# AI_XiaoZhi_4G.net
KiCad netlist of a schematic drawn in Altium Designer
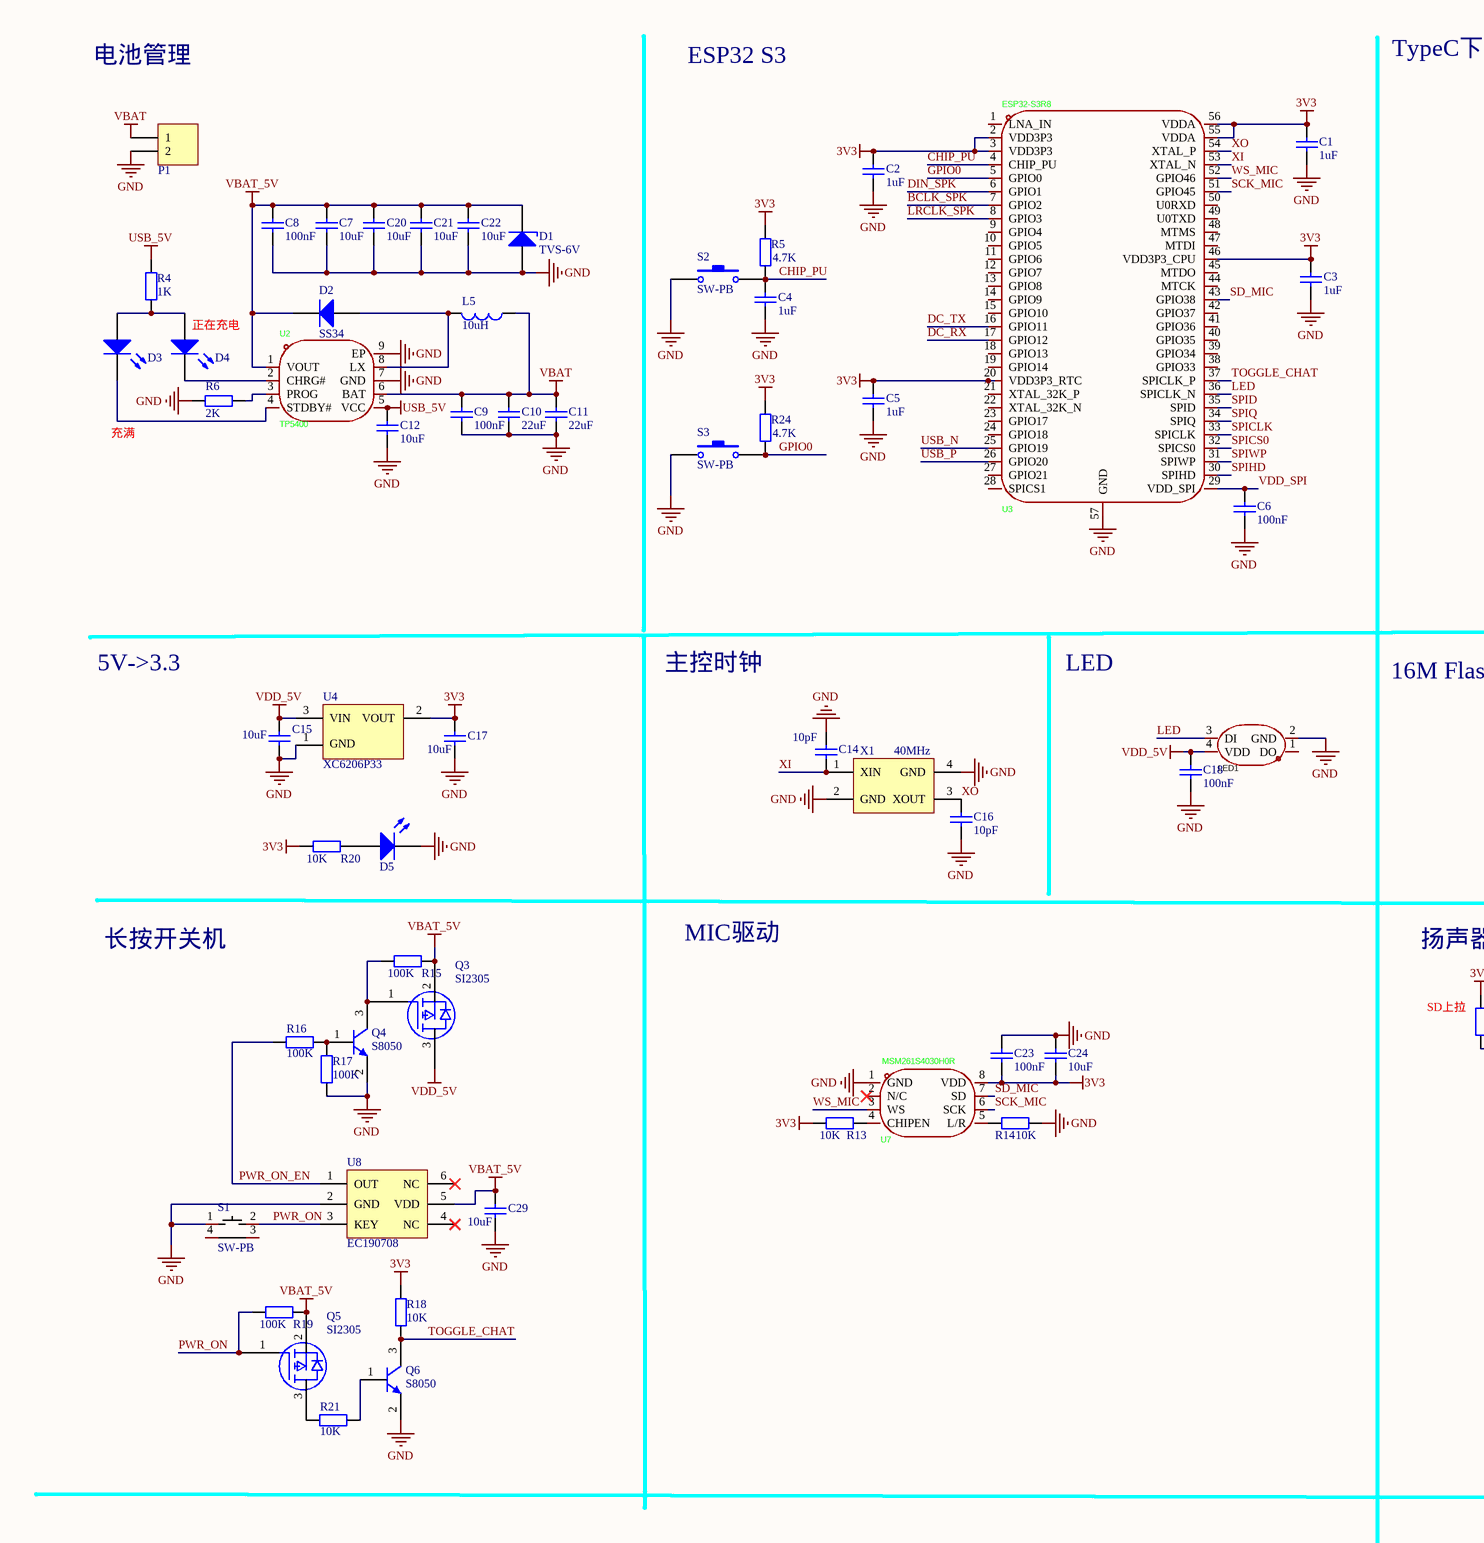
[diagram p0: AI_XiaoZhi_4G.SchDoc, left]
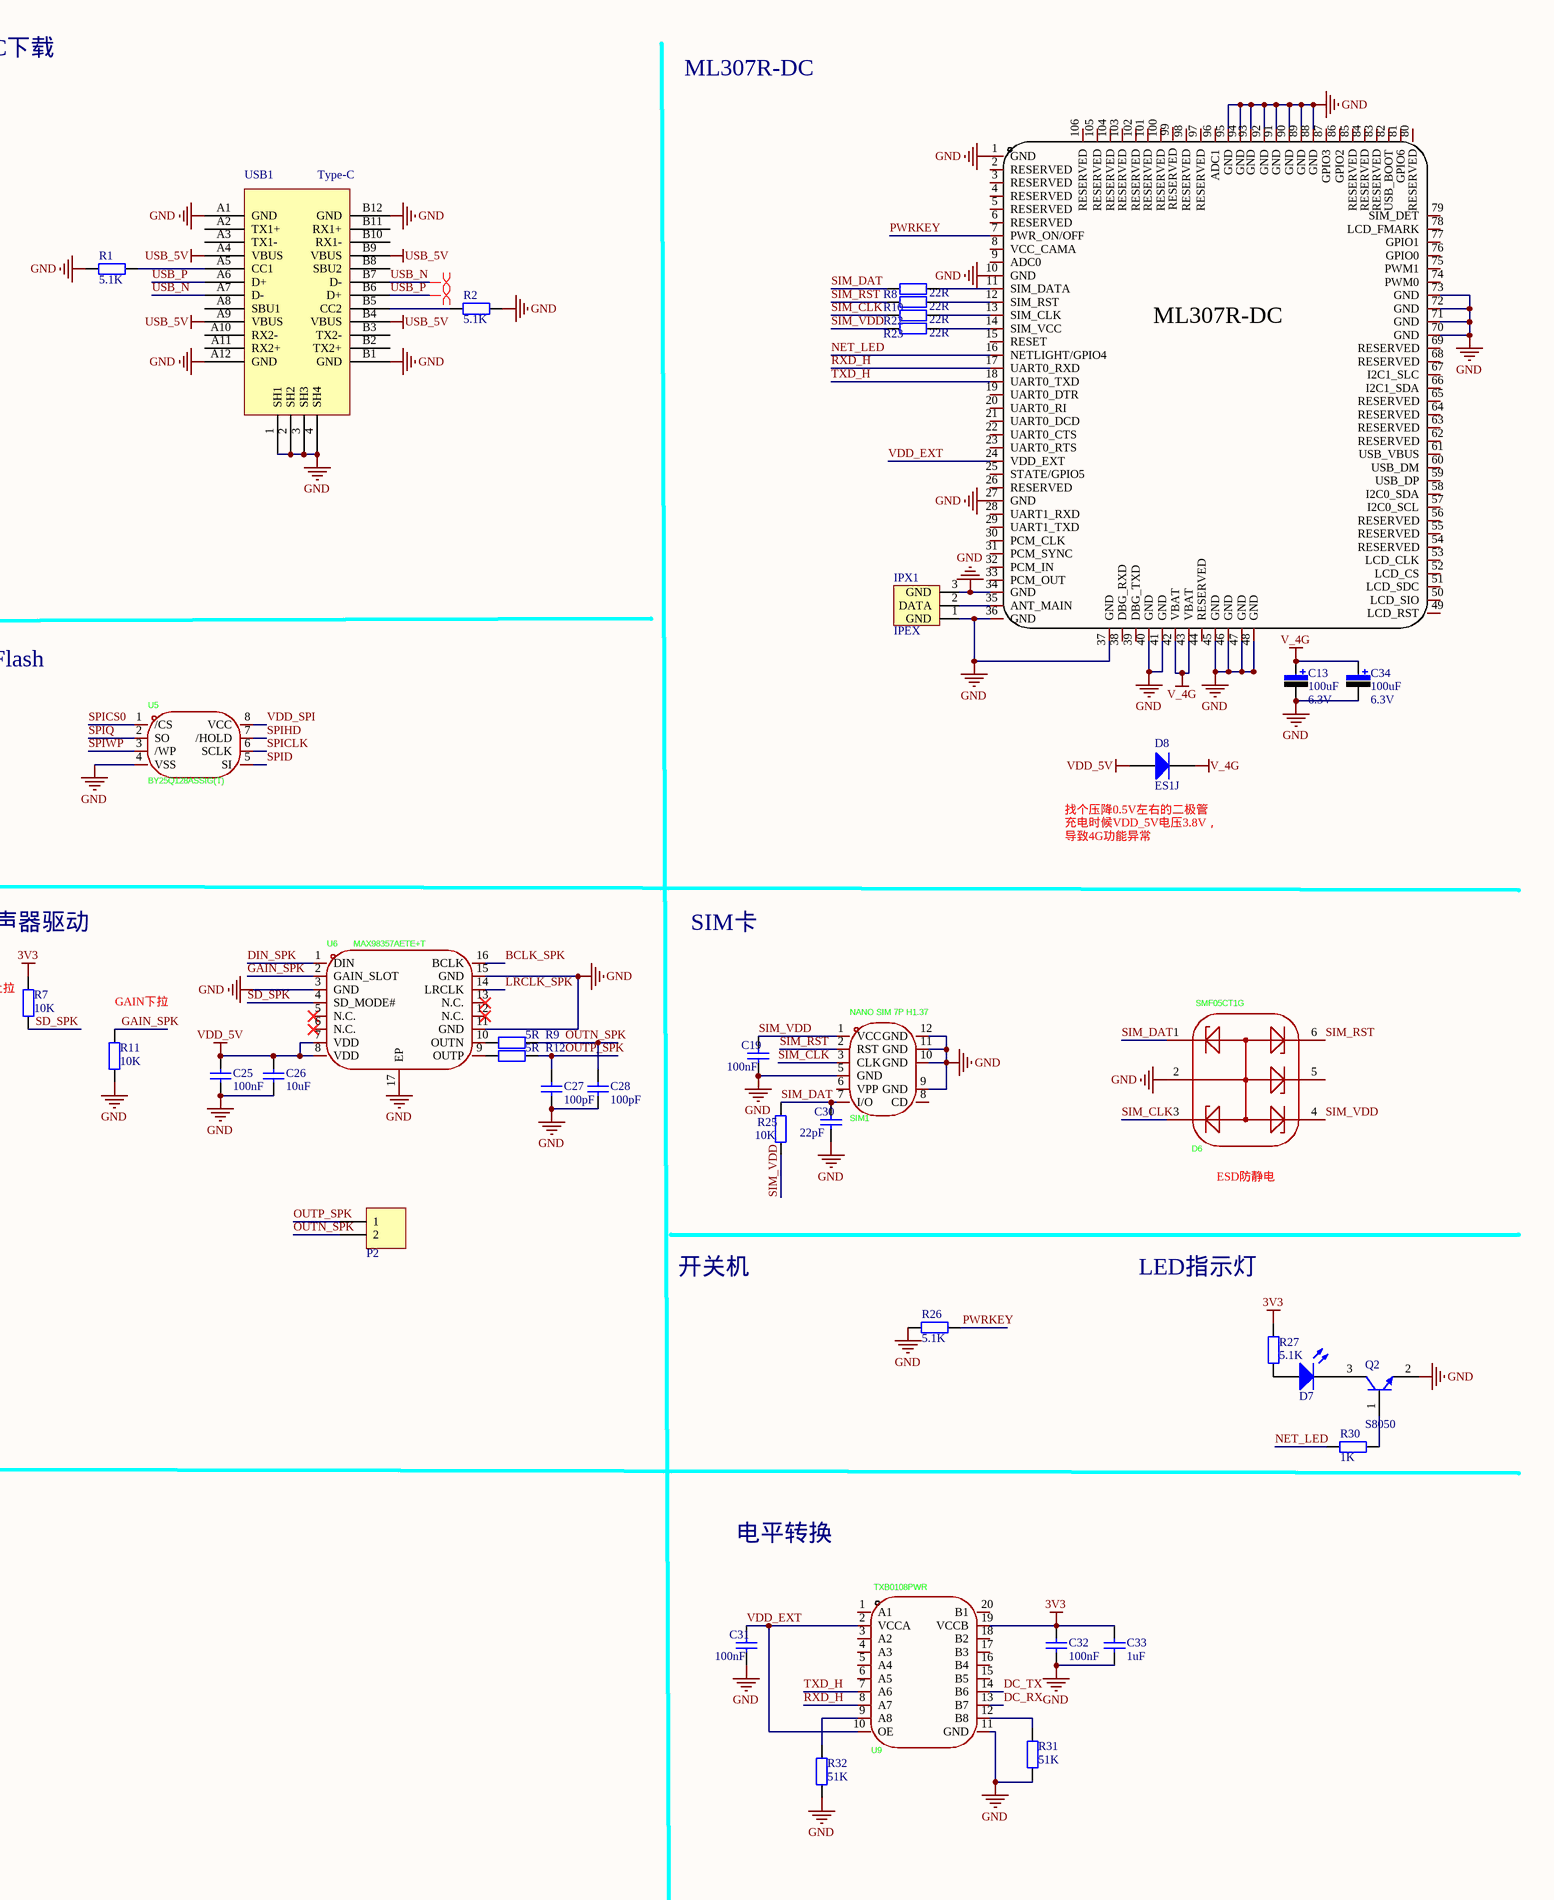
[diagram p1: AI_XiaoZhi_4G.SchDoc, right]

(export (version "E")
  (design (tool "Eeschema 10.0.6"))
  (components
    (comp (ref "C1")
      (value "1uF")
      (footprint "PCBPcblib_MXJ:0603-C")
      (description "无极性电容")
      (fields (field (name "Comment") "CAP") (field (name "PUBLISHER") "Altium Limited"))
      (libsource (lib "PCBSchlib_MXJ") (part "CAP"))
    )
    (comp (ref "C2")
      (value "1uF")
      (footprint "PCBPcblib_MXJ:0603-C")
      (description "无极性电容")
      (fields (field (name "Comment") "CAP") (field (name "PUBLISHER") "Altium Limited"))
      (libsource (lib "PCBSchlib_MXJ") (part "CAP"))
    )
    (comp (ref "C3")
      (value "1uF")
      (footprint "PCBPcblib_MXJ:0603-C")
      (description "无极性电容")
      (fields (field (name "Comment") "CAP") (field (name "PUBLISHER") "Altium Limited"))
      (libsource (lib "PCBSchlib_MXJ") (part "CAP"))
    )
    (comp (ref "C4")
      (value "1uF")
      (footprint "PCBPcblib_MXJ:0603-C")
      (description "无极性电容")
      (fields (field (name "Comment") "CAP") (field (name "PUBLISHER") "Altium Limited"))
      (libsource (lib "PCBSchlib_MXJ") (part "CAP"))
    )
    (comp (ref "C5")
      (value "1uF")
      (footprint "PCBPcblib_MXJ:0603-C")
      (description "无极性电容")
      (fields (field (name "Comment") "CAP") (field (name "PUBLISHER") "Altium Limited"))
      (libsource (lib "PCBSchlib_MXJ") (part "CAP"))
    )
    (comp (ref "C6")
      (value "100nF")
      (footprint "PCBPcblib_MXJ:0603-C")
      (description "无极性电容")
      (fields (field (name "Comment") "CAP") (field (name "PUBLISHER") "Altium Limited"))
      (libsource (lib "PCBSchlib_MXJ") (part "CAP"))
    )
    (comp (ref "C7")
      (value "10uF")
      (footprint "PCBPcblib_MXJ:0603-C")
      (description "无极性电容")
      (fields (field (name "Comment") "CAP") (field (name "PUBLISHER") "Altium Limited"))
      (libsource (lib "PCBSchlib_MXJ") (part "CAP"))
    )
    (comp (ref "C8")
      (value "100nF")
      (footprint "PCBPcblib_MXJ:0603-C")
      (description "无极性电容")
      (fields (field (name "Comment") "CAP") (field (name "PUBLISHER") "Altium Limited"))
      (libsource (lib "PCBSchlib_MXJ") (part "CAP"))
    )
    (comp (ref "C9")
      (value "100nF")
      (footprint "PCBPcblib_MXJ:0603-C")
      (description "无极性电容")
      (fields (field (name "Comment") "CAP") (field (name "PUBLISHER") "Altium Limited"))
      (libsource (lib "PCBSchlib_MXJ") (part "CAP"))
    )
    (comp (ref "C10")
      (value "22uF")
      (footprint "PCBPcblib_MXJ:0603-C")
      (description "无极性电容")
      (fields (field (name "Comment") "CAP") (field (name "PUBLISHER") "Altium Limited"))
      (libsource (lib "PCBSchlib_MXJ") (part "CAP"))
    )
    (comp (ref "C11")
      (value "22uF")
      (footprint "PCBPcblib_MXJ:0603-C")
      (description "无极性电容")
      (fields (field (name "Comment") "CAP") (field (name "PUBLISHER") "Altium Limited"))
      (libsource (lib "PCBSchlib_MXJ") (part "CAP"))
    )
    (comp (ref "C12")
      (value "10uF")
      (footprint "PCBPcblib_MXJ:0603-C")
      (description "无极性电容")
      (fields (field (name "Comment") "CAP") (field (name "PUBLISHER") "Altium Limited"))
      (libsource (lib "PCBSchlib_MXJ") (part "CAP"))
    )
    (comp (ref "C13")
      (value "100uF")
      (footprint "PCBPcblib_MXJ:CASE-A_3216")
      (description "极性电解电容")
      (fields
        (field (name "VOL") "6.3V")
        (field (name "Comment") "CAP-P")
        (field (name "PUBLISHER") "Altium Limited")
      )
      (libsource (lib "PCBSchlib_MXJ") (part "CAP-P"))
    )
    (comp (ref "C14")
      (value "10pF")
      (footprint "PCBPcblib_MXJ:0603-C")
      (description "无极性电容")
      (fields (field (name "Comment") "CAP") (field (name "PUBLISHER") "Altium Limited"))
      (libsource (lib "PCBSchlib_MXJ") (part "CAP"))
    )
    (comp (ref "C15")
      (value "10uF")
      (footprint "PCBPcblib_MXJ:0603-C")
      (description "无极性电容")
      (fields (field (name "Comment") "CAP") (field (name "PUBLISHER") "Altium Limited"))
      (libsource (lib "PCBSchlib_MXJ") (part "CAP"))
    )
    (comp (ref "C16")
      (value "10pF")
      (footprint "PCBPcblib_MXJ:0603-C")
      (description "无极性电容")
      (fields (field (name "Comment") "CAP") (field (name "PUBLISHER") "Altium Limited"))
      (libsource (lib "PCBSchlib_MXJ") (part "CAP"))
    )
    (comp (ref "C17")
      (value "10uF")
      (footprint "PCBPcblib_MXJ:0603-C")
      (description "无极性电容")
      (fields (field (name "Comment") "CAP") (field (name "PUBLISHER") "Altium Limited"))
      (libsource (lib "PCBSchlib_MXJ") (part "CAP"))
    )
    (comp (ref "C18")
      (value "100nF")
      (footprint "PCBPcblib_MXJ:0603-C")
      (description "无极性电容")
      (fields (field (name "Comment") "CAP") (field (name "PUBLISHER") "Altium Limited"))
      (libsource (lib "PCBSchlib_MXJ") (part "CAP"))
    )
    (comp (ref "C19")
      (value "100nF")
      (footprint "PCBPcblib_MXJ:0603-C")
      (description "无极性电容")
      (fields (field (name "Comment") "CAP") (field (name "PUBLISHER") "Altium Limited"))
      (libsource (lib "PCBSchlib_MXJ") (part "CAP"))
    )
    (comp (ref "C20")
      (value "10uF")
      (footprint "PCBPcblib_MXJ:0603-C")
      (description "无极性电容")
      (fields (field (name "Comment") "CAP") (field (name "PUBLISHER") "Altium Limited"))
      (libsource (lib "PCBSchlib_MXJ") (part "CAP"))
    )
    (comp (ref "C21")
      (value "10uF")
      (footprint "PCBPcblib_MXJ:0603-C")
      (description "无极性电容")
      (fields (field (name "Comment") "CAP") (field (name "PUBLISHER") "Altium Limited"))
      (libsource (lib "PCBSchlib_MXJ") (part "CAP"))
    )
    (comp (ref "C22")
      (value "10uF")
      (footprint "PCBPcblib_MXJ:0603-C")
      (description "无极性电容")
      (fields (field (name "Comment") "CAP") (field (name "PUBLISHER") "Altium Limited"))
      (libsource (lib "PCBSchlib_MXJ") (part "CAP"))
    )
    (comp (ref "C23")
      (value "100nF")
      (footprint "PCBPcblib_MXJ:0603-C")
      (description "无极性电容")
      (fields (field (name "Comment") "CAP") (field (name "PUBLISHER") "Altium Limited"))
      (libsource (lib "PCBSchlib_MXJ") (part "CAP"))
    )
    (comp (ref "C24")
      (value "10uF")
      (footprint "PCBPcblib_MXJ:0603-C")
      (description "无极性电容")
      (fields (field (name "Comment") "CAP") (field (name "PUBLISHER") "Altium Limited"))
      (libsource (lib "PCBSchlib_MXJ") (part "CAP"))
    )
    (comp (ref "C25")
      (value "100nF")
      (footprint "PCBPcblib_MXJ:0603-C")
      (description "无极性电容")
      (fields (field (name "Comment") "CAP") (field (name "PUBLISHER") "Altium Limited"))
      (libsource (lib "PCBSchlib_MXJ") (part "CAP"))
    )
    (comp (ref "C26")
      (value "10uF")
      (footprint "PCBPcblib_MXJ:0603-C")
      (description "无极性电容")
      (fields (field (name "Comment") "CAP") (field (name "PUBLISHER") "Altium Limited"))
      (libsource (lib "PCBSchlib_MXJ") (part "CAP"))
    )
    (comp (ref "C27")
      (value "100pF")
      (footprint "PCBPcblib_MXJ:0603-C")
      (description "无极性电容")
      (fields (field (name "Comment") "CAP") (field (name "PUBLISHER") "Altium Limited"))
      (libsource (lib "PCBSchlib_MXJ") (part "CAP"))
    )
    (comp (ref "C28")
      (value "100pF")
      (footprint "PCBPcblib_MXJ:0603-C")
      (description "无极性电容")
      (fields (field (name "Comment") "CAP") (field (name "PUBLISHER") "Altium Limited"))
      (libsource (lib "PCBSchlib_MXJ") (part "CAP"))
    )
    (comp (ref "C29")
      (value "10uF")
      (footprint "PCBPcblib_MXJ:0603-C")
      (description "无极性电容")
      (fields (field (name "Comment") "CAP") (field (name "PUBLISHER") "Altium Limited"))
      (libsource (lib "PCBSchlib_MXJ") (part "CAP"))
    )
    (comp (ref "C30")
      (value "22pF")
      (footprint "PCBPcblib_MXJ:0603-C")
      (description "无极性电容")
      (fields (field (name "Comment") "CAP") (field (name "PUBLISHER") "Altium Limited"))
      (libsource (lib "PCBSchlib_MXJ") (part "CAP"))
    )
    (comp (ref "C31")
      (value "100nF")
      (footprint "PCBPcblib_MXJ:0603-C")
      (description "无极性电容")
      (fields (field (name "Comment") "CAP") (field (name "PUBLISHER") "Altium Limited"))
      (libsource (lib "PCBSchlib_MXJ") (part "CAP"))
    )
    (comp (ref "C32")
      (value "100nF")
      (footprint "PCBPcblib_MXJ:0603-C")
      (description "无极性电容")
      (fields (field (name "Comment") "CAP") (field (name "PUBLISHER") "Altium Limited"))
      (libsource (lib "PCBSchlib_MXJ") (part "CAP"))
    )
    (comp (ref "C33")
      (value "1uF")
      (footprint "PCBPcblib_MXJ:0603-C")
      (description "无极性电容")
      (fields (field (name "Comment") "CAP") (field (name "PUBLISHER") "Altium Limited"))
      (libsource (lib "PCBSchlib_MXJ") (part "CAP"))
    )
    (comp (ref "C34")
      (value "100uF")
      (footprint "PCBPcblib_MXJ:CASE-A_3216")
      (description "极性电解电容")
      (fields
        (field (name "VOL") "6.3V")
        (field (name "Comment") "CAP-P")
        (field (name "PUBLISHER") "Altium Limited")
      )
      (libsource (lib "PCBSchlib_MXJ") (part "CAP-P"))
    )
    (comp (ref "D1")
      (value "TVS-6V")
      (footprint "PCBPcblib_MXJ:DIODE-SMA")
      (description "稳压二极管")
      (fields (field (name "Comment") "Diode-Z") (field (name "PUBLISHER") "Altium Limited"))
      (libsource (lib "PCBSchlib_MXJ") (part "Diode-Z"))
    )
    (comp (ref "D2")
      (value "Diode")
      (footprint "DIODE-SMA")
      (description "二极管")
      (fields (field (name "TYPE") "SS34") (field (name "PUBLISHER") "Altium Limited"))
      (libsource (lib "PCBSchlib_MXJ") (part "Diode"))
    )
    (comp (ref "D3")
      (value "LED")
      (footprint "PCBPcblib_MXJ:0603-LED")
      (description "发光二极管")
      (fields (field (name "PUBLISHER") "Altium Limited"))
      (libsource (lib "PCBSchlib_MXJ") (part "LED"))
    )
    (comp (ref "D4")
      (value "LED")
      (footprint "PCBPcblib_MXJ:0603-LED")
      (description "发光二极管")
      (fields (field (name "PUBLISHER") "Altium Limited"))
      (libsource (lib "PCBSchlib_MXJ") (part "LED"))
    )
    (comp (ref "D5")
      (value "LED")
      (footprint "PCBPcblib_MXJ:0603-LED")
      (description "发光二极管")
      (fields (field (name "PUBLISHER") "Altium Limited"))
      (libsource (lib "PCBSchlib_MXJ") (part "LED"))
    )
    (comp (ref "D6")
      (value "SMF05CT1G")
      (footprint "SOT-363")
      (fields (field (name "MANUFACTURER") "onsemi(安森美)"))
      (libsource (lib "PCBSchlib_MXJ") (part "SMF05CT1G"))
    )
    (comp (ref "D7")
      (value "LED")
      (footprint "PCBPcblib_MXJ:0603-LED")
      (description "发光二极管")
      (fields (field (name "PUBLISHER") "Altium Limited"))
      (libsource (lib "PCBSchlib_MXJ") (part "LED"))
    )
    (comp (ref "D8")
      (value "Diode")
      (footprint "DIODE-SMA")
      (description "二极管")
      (fields (field (name "TYPE") "ES1J") (field (name "PUBLISHER") "Altium Limited"))
      (libsource (lib "PCBSchlib_MXJ") (part "Diode"))
    )
    (comp (ref "IPX1")
      (value "IPEX")
      (footprint "IPEX")
      (description "IPEX座-1代")
      (libsource (lib "PCBSchlib_MXJ") (part "IPEX-1"))
    )
    (comp (ref "L5")
      (value "10uH")
      (footprint "PCBPcblib_MXJ:SMD_L4.4-W4.2")
      (description "电感")
      (fields (field (name "Comment") "Inductor") (field (name "PUBLISHER") "Altium Limited"))
      (libsource (lib "PCBSchlib_MXJ") (part "Inductor"))
    )
    (comp (ref "LED1")
      (value "XL-2020RGBC-WS2812B")
      (footprint "LED-SMD_4P-L2.0-W2.0-BR-1")
      (fields (field (name "MANUFACTURER") "XINGLIGHT(成兴光)"))
      (libsource (lib "PCBSchlib_MXJ") (part "XL-2020RGBC-WS2812B"))
    )
    (comp (ref "P1")
      (value "Header 2")
      (footprint "PCBPcblib_MXJ:CONN-SMD_2P-P1.25-HC-1.25-2PWT")
      (description "接插件")
      (fields (field (name "PUBLISHER") "Altium Limited"))
      (libsource (lib "PCBSchlib_MXJ") (part "Header 2"))
    )
    (comp (ref "P2")
      (value "Header 2")
      (footprint "PCBPcblib_MXJ:CONN-SMD_2P-P1.25-HC-1.25-2PWT")
      (description "接插件")
      (fields (field (name "PUBLISHER") "Altium Limited"))
      (libsource (lib "PCBSchlib_MXJ") (part "Header 2"))
    )
    (comp (ref "Q2")
      (value "S8050")
      (footprint "PCBPcblib_MXJ:SOT-23")
      (description "NPN三极管")
      (fields (field (name "PUBLISHER") "Altium Limited"))
      (libsource (lib "PCBSchlib_MXJ") (part "NPN_BJT"))
    )
    (comp (ref "Q3")
      (value "SI2305")
      (footprint "SOT-23")
      (description "PNP MOS管")
      (fields (field (name "Comment") "PMOS") (field (name "PUBLISHER") "Altium Limited"))
      (libsource (lib "PCBSchlib_MXJ") (part "PMOS"))
    )
    (comp (ref "Q4")
      (value "S8050")
      (footprint "PCBPcblib_MXJ:SOT-23")
      (description "NPN三极管")
      (fields (field (name "PUBLISHER") "Altium Limited"))
      (libsource (lib "PCBSchlib_MXJ") (part "NPN_BJT"))
    )
    (comp (ref "Q5")
      (value "SI2305")
      (footprint "SOT-23")
      (description "PNP MOS管")
      (fields (field (name "Comment") "PMOS") (field (name "PUBLISHER") "Altium Limited"))
      (libsource (lib "PCBSchlib_MXJ") (part "PMOS"))
    )
    (comp (ref "Q6")
      (value "S8050")
      (footprint "PCBPcblib_MXJ:SOT-23")
      (description "NPN三极管")
      (fields (field (name "PUBLISHER") "Altium Limited"))
      (libsource (lib "PCBSchlib_MXJ") (part "NPN_BJT"))
    )
    (comp (ref "R1")
      (value "5.1K")
      (footprint "PCBPcblib_MXJ:0603-R")
      (description "贴片电阻")
      (fields (field (name "Comment") "RES") (field (name "PUBLISHER") "Altium Limited"))
      (libsource (lib "") (part "RES_1"))
    )
    (comp (ref "R2")
      (value "5.1K")
      (footprint "PCBPcblib_MXJ:0603-R")
      (description "贴片电阻")
      (fields (field (name "Comment") "RES") (field (name "PUBLISHER") "Altium Limited"))
      (libsource (lib "") (part "RES_1"))
    )
    (comp (ref "R4")
      (value "1K")
      (footprint "PCBPcblib_MXJ:0603-R")
      (description "贴片电阻")
      (fields (field (name "Comment") "RES") (field (name "PUBLISHER") "Altium Limited"))
      (libsource (lib "") (part "RES_2"))
    )
    (comp (ref "R5")
      (value "4.7K")
      (footprint "PCBPcblib_MXJ:0603-R")
      (description "贴片电阻")
      (fields (field (name "Comment") "RES") (field (name "PUBLISHER") "Altium Limited"))
      (libsource (lib "") (part "RES_2"))
    )
    (comp (ref "R6")
      (value "2K")
      (footprint "PCBPcblib_MXJ:0603-R")
      (description "贴片电阻")
      (fields (field (name "Comment") "RES") (field (name "PUBLISHER") "Altium Limited"))
      (libsource (lib "") (part "RES_1"))
    )
    (comp (ref "R7")
      (value "10K")
      (footprint "PCBPcblib_MXJ:0603-R")
      (description "贴片电阻")
      (fields (field (name "Comment") "RES") (field (name "PUBLISHER") "Altium Limited"))
      (libsource (lib "") (part "RES_2"))
    )
    (comp (ref "R8")
      (value "22R")
      (footprint "PCBPcblib_MXJ:0603-R")
      (description "贴片电阻")
      (fields (field (name "Comment") "RES") (field (name "PUBLISHER") "Altium Limited"))
      (libsource (lib "") (part "RES_1"))
    )
    (comp (ref "R9")
      (value "5R")
      (footprint "PCBPcblib_MXJ:0603-R")
      (description "贴片电阻")
      (fields (field (name "Comment") "RES") (field (name "PUBLISHER") "Altium Limited"))
      (libsource (lib "PCBSchlib_MXJ") (part "RES"))
    )
    (comp (ref "R10")
      (value "22R")
      (footprint "PCBPcblib_MXJ:0603-R")
      (description "贴片电阻")
      (fields (field (name "Comment") "RES") (field (name "PUBLISHER") "Altium Limited"))
      (libsource (lib "") (part "RES_1"))
    )
    (comp (ref "R11")
      (value "10K")
      (footprint "PCBPcblib_MXJ:0603-R")
      (description "贴片电阻")
      (fields (field (name "Comment") "RES") (field (name "PUBLISHER") "Altium Limited"))
      (libsource (lib "") (part "RES_2"))
    )
    (comp (ref "R12")
      (value "5R")
      (footprint "PCBPcblib_MXJ:0603-R")
      (description "贴片电阻")
      (fields (field (name "Comment") "RES") (field (name "PUBLISHER") "Altium Limited"))
      (libsource (lib "PCBSchlib_MXJ") (part "RES"))
    )
    (comp (ref "R13")
      (value "10K")
      (footprint "PCBPcblib_MXJ:0603-R")
      (description "贴片电阻")
      (fields (field (name "Comment") "RES") (field (name "PUBLISHER") "Altium Limited"))
      (libsource (lib "") (part "RES_1"))
    )
    (comp (ref "R14")
      (value "10K")
      (footprint "PCBPcblib_MXJ:0603-R")
      (description "贴片电阻")
      (fields (field (name "Comment") "RES") (field (name "PUBLISHER") "Altium Limited"))
      (libsource (lib "PCBSchlib_MXJ") (part "RES"))
    )
    (comp (ref "R15")
      (value "100K")
      (footprint "PCBPcblib_MXJ:0603-R")
      (description "贴片电阻")
      (fields (field (name "Comment") "RES") (field (name "PUBLISHER") "Altium Limited"))
      (libsource (lib "") (part "RES_1"))
    )
    (comp (ref "R16")
      (value "100K")
      (footprint "PCBPcblib_MXJ:0603-R")
      (description "贴片电阻")
      (fields (field (name "Comment") "RES") (field (name "PUBLISHER") "Altium Limited"))
      (libsource (lib "PCBSchlib_MXJ") (part "RES"))
    )
    (comp (ref "R17")
      (value "100K")
      (footprint "PCBPcblib_MXJ:0603-R")
      (description "贴片电阻")
      (fields (field (name "Comment") "RES") (field (name "PUBLISHER") "Altium Limited"))
      (libsource (lib "") (part "RES_3"))
    )
    (comp (ref "R18")
      (value "10K")
      (footprint "PCBPcblib_MXJ:0603-R")
      (description "贴片电阻")
      (fields (field (name "Comment") "RES") (field (name "PUBLISHER") "Altium Limited"))
      (libsource (lib "") (part "RES_3"))
    )
    (comp (ref "R19")
      (value "100K")
      (footprint "PCBPcblib_MXJ:0603-R")
      (description "贴片电阻")
      (fields (field (name "Comment") "RES") (field (name "PUBLISHER") "Altium Limited"))
      (libsource (lib "") (part "RES_1"))
    )
    (comp (ref "R20")
      (value "10K")
      (footprint "PCBPcblib_MXJ:0603-R")
      (description "贴片电阻")
      (fields (field (name "Comment") "RES") (field (name "PUBLISHER") "Altium Limited"))
      (libsource (lib "") (part "RES_1"))
    )
    (comp (ref "R21")
      (value "10K")
      (footprint "PCBPcblib_MXJ:0603-R")
      (description "贴片电阻")
      (fields (field (name "Comment") "RES") (field (name "PUBLISHER") "Altium Limited"))
      (libsource (lib "PCBSchlib_MXJ") (part "RES"))
    )
    (comp (ref "R22")
      (value "22R")
      (footprint "PCBPcblib_MXJ:0603-R")
      (description "贴片电阻")
      (fields (field (name "Comment") "RES") (field (name "PUBLISHER") "Altium Limited"))
      (libsource (lib "") (part "RES_1"))
    )
    (comp (ref "R23")
      (value "22R")
      (footprint "PCBPcblib_MXJ:0603-R")
      (description "贴片电阻")
      (fields (field (name "Comment") "RES") (field (name "PUBLISHER") "Altium Limited"))
      (libsource (lib "") (part "RES_1"))
    )
    (comp (ref "R24")
      (value "4.7K")
      (footprint "PCBPcblib_MXJ:0603-R")
      (description "贴片电阻")
      (fields (field (name "Comment") "RES") (field (name "PUBLISHER") "Altium Limited"))
      (libsource (lib "") (part "RES_2"))
    )
    (comp (ref "R25")
      (value "10K")
      (footprint "PCBPcblib_MXJ:0603-R")
      (description "贴片电阻")
      (fields (field (name "Comment") "RES") (field (name "PUBLISHER") "Altium Limited"))
      (libsource (lib "") (part "RES_3"))
    )
    (comp (ref "R26")
      (value "5.1K")
      (footprint "PCBPcblib_MXJ:0603-R")
      (description "贴片电阻")
      (fields (field (name "Comment") "RES") (field (name "PUBLISHER") "Altium Limited"))
      (libsource (lib "") (part "RES_1"))
    )
    (comp (ref "R27")
      (value "5.1K")
      (footprint "PCBPcblib_MXJ:0603-R")
      (description "贴片电阻")
      (fields (field (name "Comment") "RES") (field (name "PUBLISHER") "Altium Limited"))
      (libsource (lib "") (part "RES_2"))
    )
    (comp (ref "R30")
      (value "1K")
      (footprint "PCBPcblib_MXJ:0603-R")
      (description "贴片电阻")
      (fields (field (name "Comment") "RES") (field (name "PUBLISHER") "Altium Limited"))
      (libsource (lib "") (part "RES_1"))
    )
    (comp (ref "R31")
      (value "51K")
      (footprint "PCBPcblib_MXJ:0603-R")
      (description "贴片电阻")
      (fields (field (name "Comment") "RES") (field (name "PUBLISHER") "Altium Limited"))
      (libsource (lib "") (part "RES_3"))
    )
    (comp (ref "R32")
      (value "51K")
      (footprint "PCBPcblib_MXJ:0603-R")
      (description "贴片电阻")
      (fields (field (name "Comment") "RES") (field (name "PUBLISHER") "Altium Limited"))
      (libsource (lib "") (part "RES_3"))
    )
    (comp (ref "S1")
      (value "SW-PB")
      (footprint "PCBPcblib_MXJ:SW_TS")
      (description "微动开关")
      (fields (field (name "PUBLISHER") "Altium Limited"))
      (libsource (lib "PCBSchlib_MXJ") (part "SW-TS"))
    )
    (comp (ref "S2")
      (value "SW-PB")
      (footprint "PCBPcblib_MXJ:SW-SMD_L3.9-W3.0-P4.45")
      (description "微动开关")
      (fields (field (name "PUBLISHER") "Altium Limited"))
      (libsource (lib "PCBSchlib_MXJ") (part "SW-PB"))
    )
    (comp (ref "S3")
      (value "SW-PB")
      (footprint "PCBPcblib_MXJ:SW-SMD_L3.9-W3.0-P4.45")
      (description "微动开关")
      (fields (field (name "PUBLISHER") "Altium Limited"))
      (libsource (lib "PCBSchlib_MXJ") (part "SW-PB"))
    )
    (comp (ref "SIM1")
      (value "NANO SIM 7P H1.37")
      (footprint "SIM-SMD_NANO-SIM-7P-H1.37")
      (fields (field (name "MANUFACTURER") "SHOU HAN(首韩)"))
      (libsource (lib "PCBSchlib_MXJ") (part "NANO SIM 7P H1.37"))
    )
    (comp (ref "U1")
      (value "ML307R-DC")
      (footprint "LGA-109_L17.7-W15.8-AIR780E")
      (fields (field (name "MANUFACTURER PART") "ML307A-DNLM"))
      (libsource (lib "PCBSchlib_MXJ") (part "ML307R-DC"))
    )
    (comp (ref "U2")
      (value "TP5400")
      (footprint "ESOP-8")
      (description "单节锂电池充电管理模块")
      (fields (field (name "MANUFACTURER") "TOPPOWER(南京拓微)"))
      (libsource (lib "PCBSchlib_MXJ") (part "TP5400"))
    )
    (comp (ref "U3")
      (value "ESP32-S3R8")
      (footprint "QFN-56_L7.0-W7.0-P0.40-TL-EP4.0")
      (fields (field (name "MANUFACTURER") "ESPRESSIF(乐鑫)"))
      (libsource (lib "PCBSchlib_MXJ") (part "ESP32-S3R8"))
    )
    (comp (ref "U4")
      (value "XC6206P33")
      (footprint "SOT-23")
      (description "LDO稳压芯片")
      (libsource (lib "PCBSchlib_MXJ") (part "XC6206PXXX"))
    )
    (comp (ref "U5")
      (value "BY25Q128ASSIG(T)")
      (footprint "SOIC-8")
      (description "flash")
      (fields (field (name "MANUFACTURER") "BOYAMICRO(博雅)"))
      (libsource (lib "PCBSchlib_MXJ") (part "BY25Q128ASSIG(T)"))
    )
    (comp (ref "U6")
      (value "MAX98357AETE+T")
      (footprint "TQFN-16")
      (description "扬声器驱动芯片")
      (fields (field (name "MANUFACTURER") "ADI(亚德诺)/MAXIM(美信)"))
      (libsource (lib "PCBSchlib_MXJ") (part "MAX98357AETE+T"))
    )
    (comp (ref "U7")
      (value "MSM261S4030H0R")
      (footprint "MIC-SMD_8P-L4.0-W3.0-P1.00-BR")
      (fields (field (name "MANUFACTURER") "MEMS(敏芯微)"))
      (libsource (lib "PCBSchlib_MXJ") (part "MIC"))
    )
    (comp (ref "U8")
      (value "EC190708")
      (footprint "PCBPcblib_MXJ:SOT-23-6")
      (description "长按开关机")
      (libsource (lib "PCBSchlib_MXJ") (part "EC190708"))
    )
    (comp (ref "U9")
      (value "TXB0108PWR")
      (footprint "TSSOP-20_L6.5-W4.4-P0.65-LS6.4-BL")
      (fields (field (name "MANUFACTURER") "TI(德州仪器)"))
      (libsource (lib "PCBSchlib_MXJ") (part "TXB0108PWR"))
    )
    (comp (ref "USB1")
      (value "Type-C")
      (footprint "Type-C-TOP")
      (description "16Pins TYPEC")
      (libsource (lib "PCBSchlib_MXJ") (part "USB-Type-C-TOP"))
    )
    (comp (ref "X1")
      (value "40MHz")
      (footprint "PCBPcblib_MXJ:2520-XTAL")
      (description "无源晶振")
      (fields (field (name "MF") "ECS International") (field (name "MP") "ECS-3225S30-240-EN-TR"))
      (libsource (lib "PCBSchlib_MXJ") (part "XTAL4G"))
    )
  )
  (nets
    (net (code "1") (name "/BCLK_SPK") (class "Default")
      (node (ref "U3") (pin "7") (pinfunction "GPIO2_7") (pintype "passive"))
      (node (ref "U6") (pin "16") (pinfunction "BCLK_16") (pintype "passive"))
    )
    (net (code "2") (name "/CHIP_PU") (class "Default")
      (node (ref "C4") (pin "1") (pinfunction "1_1") (pintype "passive"))
      (node (ref "R5") (pin "1") (pinfunction "1_1") (pintype "passive"))
      (node (ref "S2") (pin "2") (pinfunction "2_2") (pintype "passive"))
      (node (ref "U3") (pin "4") (pinfunction "CHIP_PU_4") (pintype "passive"))
    )
    (net (code "3") (name "/DC_RX") (class "Default")
      (node (ref "U3") (pin "17") (pinfunction "GPIO12_17") (pintype "passive"))
      (node (ref "U9") (pin "13") (pinfunction "B7_13") (pintype "passive"))
    )
    (net (code "4") (name "/DC_TX") (class "Default")
      (node (ref "U3") (pin "16") (pinfunction "GPIO11_16") (pintype "passive"))
      (node (ref "U9") (pin "14") (pinfunction "B6_14") (pintype "passive"))
    )
    (net (code "5") (name "/DIN_SPK") (class "Default")
      (node (ref "U3") (pin "6") (pinfunction "GPIO1_6") (pintype "passive"))
      (node (ref "U6") (pin "1") (pinfunction "DIN_1") (pintype "passive"))
    )
    (net (code "6") (name "/GAIN_SPK") (class "Default")
      (node (ref "R11") (pin "2") (pinfunction "2_2") (pintype "passive"))
      (node (ref "U6") (pin "2") (pinfunction "GAIN_SLOT_2") (pintype "passive"))
    )
    (net (code "7") (name "/GPIO0") (class "Default")
      (node (ref "R24") (pin "1") (pinfunction "1_1") (pintype "passive"))
      (node (ref "S3") (pin "2") (pinfunction "2_2") (pintype "passive"))
      (node (ref "U3") (pin "5") (pinfunction "GPIO0_5") (pintype "passive"))
    )
    (net (code "8") (name "/LED") (class "Default")
      (node (ref "LED1") (pin "3") (pinfunction "DI_3") (pintype "passive"))
      (node (ref "U3") (pin "36") (pinfunction "SPICLK_N_36") (pintype "passive"))
    )
    (net (code "9") (name "/LRCLK_SPK") (class "Default")
      (node (ref "U3") (pin "8") (pinfunction "GPIO3_8") (pintype "passive"))
      (node (ref "U6") (pin "14") (pinfunction "LRCLK_14") (pintype "passive"))
    )
    (net (code "10") (name "/NET_LED") (class "Default")
      (node (ref "R30") (pin "2") (pinfunction "2_2") (pintype "passive"))
      (node (ref "U1") (pin "16") (pinfunction "NETLIGHT/GPIO4_16") (pintype "passive"))
    )
    (net (code "11") (name "/OUTN_SPK") (class "Default")
      (node (ref "C28") (pin "1") (pinfunction "1_1") (pintype "passive"))
      (node (ref "P2") (pin "2") (pinfunction "2_2") (pintype "passive"))
      (node (ref "R9") (pin "2") (pinfunction "2_2") (pintype "passive"))
    )
    (net (code "12") (name "/OUTP_SPK") (class "Default")
      (node (ref "C27") (pin "1") (pinfunction "1_1") (pintype "passive"))
      (node (ref "P2") (pin "1") (pinfunction "1_1") (pintype "passive"))
      (node (ref "R12") (pin "2") (pinfunction "2_2") (pintype "passive"))
    )
    (net (code "13") (name "/PWRKEY") (class "Default")
      (node (ref "R26") (pin "1") (pinfunction "1_1") (pintype "passive"))
      (node (ref "U1") (pin "7") (pinfunction "PWR_ON/OFF_7") (pintype "passive"))
    )
    (net (code "14") (name "/PWR_ON") (class "Default")
      (node (ref "Q5") (pin "1") (pinfunction "G_1") (pintype "passive"))
      (node (ref "R19") (pin "2") (pinfunction "2_2") (pintype "passive"))
      (node (ref "S1") (pin "2") (pinfunction "2_2") (pintype "passive"))
      (node (ref "U8") (pin "3") (pinfunction "KEY_3") (pintype "passive"))
    )
    (net (code "15") (name "/PWR_ON_EN") (class "Default")
      (node (ref "R16") (pin "1") (pinfunction "1_1") (pintype "passive"))
      (node (ref "U8") (pin "1") (pinfunction "OUT_1") (pintype "passive"))
    )
    (net (code "16") (name "/RXD_H") (class "Default")
      (node (ref "U1") (pin "17") (pinfunction "UART0_RXD_17") (pintype "passive"))
      (node (ref "U9") (pin "8") (pinfunction "A7_8") (pintype "passive"))
    )
    (net (code "17") (name "/SCK_MIC") (class "Default")
      (node (ref "U3") (pin "51") (pinfunction "GPIO45_51") (pintype "passive"))
      (node (ref "U7") (pin "6") (pinfunction "SCK_6") (pintype "passive"))
    )
    (net (code "18") (name "/SD_MIC") (class "Default")
      (node (ref "U3") (pin "43") (pinfunction "GPIO38_43") (pintype "passive"))
      (node (ref "U7") (pin "7") (pinfunction "SD_7") (pintype "passive"))
    )
    (net (code "19") (name "/SD_SPK") (class "Default")
      (node (ref "R7") (pin "1") (pinfunction "1_1") (pintype "passive"))
      (node (ref "U6") (pin "4") (pinfunction "SD_MODE#_4") (pintype "passive"))
    )
    (net (code "20") (name "/SIM_CLK") (class "Default")
      (node (ref "D6") (pin "3") (pinfunction "3_3") (pintype "passive"))
      (node (ref "R22") (pin "2") (pinfunction "2_2") (pintype "passive"))
      (node (ref "SIM1") (pin "3") (pinfunction "CLK_3") (pintype "passive"))
    )
    (net (code "21") (name "/SIM_DAT") (class "Default")
      (node (ref "C30") (pin "2") (pinfunction "2_2") (pintype "passive"))
      (node (ref "D6") (pin "1") (pinfunction "1_1") (pintype "passive"))
      (node (ref "R25") (pin "1") (pinfunction "1_1") (pintype "passive"))
      (node (ref "R8") (pin "2") (pinfunction "2_2") (pintype "passive"))
      (node (ref "SIM1") (pin "7") (pinfunction "I/O_7") (pintype "passive"))
    )
    (net (code "22") (name "/SIM_RST") (class "Default")
      (node (ref "D6") (pin "6") (pinfunction "6_6") (pintype "passive"))
      (node (ref "R10") (pin "2") (pinfunction "2_2") (pintype "passive"))
      (node (ref "SIM1") (pin "2") (pinfunction "RST_2") (pintype "passive"))
    )
    (net (code "23") (name "/SIM_VDD") (class "Default")
      (node (ref "C19") (pin "2") (pinfunction "2_2") (pintype "passive"))
      (node (ref "D6") (pin "4") (pinfunction "4_4") (pintype "passive"))
      (node (ref "R23") (pin "2") (pinfunction "2_2") (pintype "passive"))
      (node (ref "R25") (pin "2") (pinfunction "2_2") (pintype "passive"))
      (node (ref "SIM1") (pin "1") (pinfunction "VCC_1") (pintype "passive"))
    )
    (net (code "24") (name "/SPICLK") (class "Default")
      (node (ref "U3") (pin "33") (pinfunction "SPICLK_33") (pintype "passive"))
      (node (ref "U5") (pin "6") (pinfunction "SCLK_6") (pintype "passive"))
    )
    (net (code "25") (name "/SPICS0") (class "Default")
      (node (ref "U3") (pin "32") (pinfunction "SPICS0_32") (pintype "passive"))
      (node (ref "U5") (pin "1") (pinfunction "/CS_1") (pintype "passive"))
    )
    (net (code "26") (name "/SPID") (class "Default")
      (node (ref "U3") (pin "35") (pinfunction "SPID_35") (pintype "passive"))
      (node (ref "U5") (pin "5") (pinfunction "SI_5") (pintype "passive"))
    )
    (net (code "27") (name "/SPIHD") (class "Default")
      (node (ref "U3") (pin "30") (pinfunction "SPIHD_30") (pintype "passive"))
      (node (ref "U5") (pin "7") (pinfunction "/HOLD_7") (pintype "passive"))
    )
    (net (code "28") (name "/SPIQ") (class "Default")
      (node (ref "U3") (pin "34") (pinfunction "SPIQ_34") (pintype "passive"))
      (node (ref "U5") (pin "2") (pinfunction "SO_2") (pintype "passive"))
    )
    (net (code "29") (name "/SPIWP") (class "Default")
      (node (ref "U3") (pin "31") (pinfunction "SPIWP_31") (pintype "passive"))
      (node (ref "U5") (pin "3") (pinfunction "/WP_3") (pintype "passive"))
    )
    (net (code "30") (name "/TOGGLE_CHAT") (class "Default")
      (node (ref "Q6") (pin "3") (pinfunction "C_3") (pintype "passive"))
      (node (ref "R18") (pin "2") (pinfunction "2_2") (pintype "passive"))
      (node (ref "U3") (pin "37") (pinfunction "SPICLK_P_37") (pintype "passive"))
    )
    (net (code "31") (name "/TXD_H") (class "Default")
      (node (ref "U1") (pin "18") (pinfunction "UART0_TXD_18") (pintype "passive"))
      (node (ref "U9") (pin "7") (pinfunction "A6_7") (pintype "passive"))
    )
    (net (code "32") (name "/USB_N") (class "Default")
      (node (ref "U3") (pin "25") (pinfunction "GPIO19_25") (pintype "passive"))
      (node (ref "USB1") (pin "A7") (pinfunction "D-_A7") (pintype "passive"))
      (node (ref "USB1") (pin "B7") (pinfunction "D-_B7") (pintype "passive"))
    )
    (net (code "33") (name "/USB_P") (class "Default")
      (node (ref "U3") (pin "26") (pinfunction "GPIO20_26") (pintype "passive"))
      (node (ref "USB1") (pin "A6") (pinfunction "D+_A6") (pintype "passive"))
      (node (ref "USB1") (pin "B6") (pinfunction "D+_B6") (pintype "passive"))
    )
    (net (code "34") (name "/VDD_EXT") (class "Default")
      (node (ref "C31") (pin "2") (pinfunction "2_2") (pintype "passive"))
      (node (ref "U1") (pin "24") (pinfunction "VDD_EXT_24") (pintype "passive"))
      (node (ref "U9") (pin "10") (pinfunction "OE_10") (pintype "passive"))
      (node (ref "U9") (pin "2") (pinfunction "VCCA_2") (pintype "passive"))
    )
    (net (code "35") (name "/VDD_SPI") (class "Default")
      (node (ref "C6") (pin "2") (pinfunction "2_2") (pintype "passive"))
      (node (ref "U3") (pin "29") (pinfunction "VDD_SPI_29") (pintype "passive"))
      (node (ref "U5") (pin "8") (pinfunction "VCC_8") (pintype "passive"))
    )
    (net (code "36") (name "/WS_MIC") (class "Default")
      (node (ref "U3") (pin "52") (pinfunction "GPIO46_52") (pintype "passive"))
      (node (ref "U7") (pin "3") (pinfunction "WS_3") (pintype "passive"))
    )
    (net (code "37") (name "/XI") (class "Default")
      (node (ref "C14") (pin "1") (pinfunction "1_1") (pintype "passive"))
      (node (ref "U3") (pin "53") (pinfunction "XTAL_N_53") (pintype "passive"))
      (node (ref "X1") (pin "1") (pinfunction "XIN_1") (pintype "passive"))
    )
    (net (code "38") (name "/XO") (class "Default")
      (node (ref "C16") (pin "1") (pinfunction "1_1") (pintype "passive"))
      (node (ref "U3") (pin "54") (pinfunction "XTAL_P_54") (pintype "passive"))
      (node (ref "X1") (pin "3") (pinfunction "XOUT_3") (pintype "passive"))
    )
    (net (code "39") (name "3V3") (class "Default")
      (node (ref "C1") (pin "2") (pinfunction "2_2") (pintype "passive"))
      (node (ref "C17") (pin "2") (pinfunction "2_2") (pintype "passive"))
      (node (ref "C2") (pin "1") (pinfunction "1_1") (pintype "passive"))
      (node (ref "C23") (pin "1") (pinfunction "1_1") (pintype "passive"))
      (node (ref "C24") (pin "1") (pinfunction "1_1") (pintype "passive"))
      (node (ref "C3") (pin "2") (pinfunction "2_2") (pintype "passive"))
      (node (ref "C32") (pin "2") (pinfunction "2_2") (pintype "passive"))
      (node (ref "C33") (pin "2") (pinfunction "2_2") (pintype "passive"))
      (node (ref "C5") (pin "1") (pinfunction "1_1") (pintype "passive"))
      (node (ref "R13") (pin "2") (pinfunction "2_2") (pintype "passive"))
      (node (ref "R18") (pin "1") (pinfunction "1_1") (pintype "passive"))
      (node (ref "R20") (pin "2") (pinfunction "2_2") (pintype "passive"))
      (node (ref "R24") (pin "2") (pinfunction "2_2") (pintype "passive"))
      (node (ref "R27") (pin "2") (pinfunction "2_2") (pintype "passive"))
      (node (ref "R5") (pin "2") (pinfunction "2_2") (pintype "passive"))
      (node (ref "R7") (pin "2") (pinfunction "2_2") (pintype "passive"))
      (node (ref "U3") (pin "2") (pinfunction "VDD3P3_2") (pintype "passive"))
      (node (ref "U3") (pin "20") (pinfunction "VDD3P3_RTC_20") (pintype "passive"))
      (node (ref "U3") (pin "3") (pinfunction "VDD3P3_3") (pintype "passive"))
      (node (ref "U3") (pin "46") (pinfunction "VDD3P3_CPU_46") (pintype "passive"))
      (node (ref "U3") (pin "55") (pinfunction "VDDA_55") (pintype "passive"))
      (node (ref "U3") (pin "56") (pinfunction "VDDA_56") (pintype "passive"))
      (node (ref "U4") (pin "2") (pinfunction "VOUT_2") (pintype "passive"))
      (node (ref "U7") (pin "8") (pinfunction "VDD_8") (pintype "passive"))
      (node (ref "U9") (pin "19") (pinfunction "VCCB_19") (pintype "passive"))
    )
    (net (code "40") (name "GND") (class "Default")
      (node (ref "C1") (pin "1") (pinfunction "1_1") (pintype "passive"))
      (node (ref "C10") (pin "2") (pinfunction "2_2") (pintype "passive"))
      (node (ref "C11") (pin "2") (pinfunction "2_2") (pintype "passive"))
      (node (ref "C12") (pin "2") (pinfunction "2_2") (pintype "passive"))
      (node (ref "C13") (pin "2") (pinfunction "2_2") (pintype "passive"))
      (node (ref "C14") (pin "2") (pinfunction "2_2") (pintype "passive"))
      (node (ref "C15") (pin "1") (pinfunction "1_1") (pintype "passive"))
      (node (ref "C16") (pin "2") (pinfunction "2_2") (pintype "passive"))
      (node (ref "C17") (pin "1") (pinfunction "1_1") (pintype "passive"))
      (node (ref "C18") (pin "1") (pinfunction "1_1") (pintype "passive"))
      (node (ref "C19") (pin "1") (pinfunction "1_1") (pintype "passive"))
      (node (ref "C2") (pin "2") (pinfunction "2_2") (pintype "passive"))
      (node (ref "C20") (pin "2") (pinfunction "2_2") (pintype "passive"))
      (node (ref "C21") (pin "2") (pinfunction "2_2") (pintype "passive"))
      (node (ref "C22") (pin "2") (pinfunction "2_2") (pintype "passive"))
      (node (ref "C23") (pin "2") (pinfunction "2_2") (pintype "passive"))
      (node (ref "C24") (pin "2") (pinfunction "2_2") (pintype "passive"))
      (node (ref "C25") (pin "2") (pinfunction "2_2") (pintype "passive"))
      (node (ref "C26") (pin "2") (pinfunction "2_2") (pintype "passive"))
      (node (ref "C27") (pin "2") (pinfunction "2_2") (pintype "passive"))
      (node (ref "C28") (pin "2") (pinfunction "2_2") (pintype "passive"))
      (node (ref "C29") (pin "1") (pinfunction "1_1") (pintype "passive"))
      (node (ref "C3") (pin "1") (pinfunction "1_1") (pintype "passive"))
      (node (ref "C30") (pin "1") (pinfunction "1_1") (pintype "passive"))
      (node (ref "C31") (pin "1") (pinfunction "1_1") (pintype "passive"))
      (node (ref "C32") (pin "1") (pinfunction "1_1") (pintype "passive"))
      (node (ref "C33") (pin "1") (pinfunction "1_1") (pintype "passive"))
      (node (ref "C34") (pin "2") (pinfunction "2_2") (pintype "passive"))
      (node (ref "C4") (pin "2") (pinfunction "2_2") (pintype "passive"))
      (node (ref "C5") (pin "2") (pinfunction "2_2") (pintype "passive"))
      (node (ref "C6") (pin "1") (pinfunction "1_1") (pintype "passive"))
      (node (ref "C7") (pin "2") (pinfunction "2_2") (pintype "passive"))
      (node (ref "C8") (pin "2") (pinfunction "2_2") (pintype "passive"))
      (node (ref "C9") (pin "2") (pinfunction "2_2") (pintype "passive"))
      (node (ref "D1") (pin "1") (pinfunction "A_1") (pintype "passive"))
      (node (ref "D5") (pin "2") (pinfunction "K_2") (pintype "passive"))
      (node (ref "D6") (pin "2") (pinfunction "2_2") (pintype "passive"))
      (node (ref "IPX1") (pin "1") (pinfunction "GND_1") (pintype "passive"))
      (node (ref "IPX1") (pin "3") (pinfunction "GND_3") (pintype "passive"))
      (node (ref "LED1") (pin "2") (pinfunction "GND_2") (pintype "passive"))
      (node (ref "P1") (pin "2") (pinfunction "2_2") (pintype "passive"))
      (node (ref "Q2") (pin "2") (pinfunction "E_2") (pintype "passive"))
      (node (ref "Q4") (pin "2") (pinfunction "E_2") (pintype "passive"))
      (node (ref "Q6") (pin "2") (pinfunction "E_2") (pintype "passive"))
      (node (ref "R1") (pin "2") (pinfunction "2_2") (pintype "passive"))
      (node (ref "R11") (pin "1") (pinfunction "1_1") (pintype "passive"))
      (node (ref "R14") (pin "2") (pinfunction "2_2") (pintype "passive"))
      (node (ref "R17") (pin "2") (pinfunction "2_2") (pintype "passive"))
      (node (ref "R2") (pin "1") (pinfunction "1_1") (pintype "passive"))
      (node (ref "R26") (pin "2") (pinfunction "2_2") (pintype "passive"))
      (node (ref "R31") (pin "2") (pinfunction "2_2") (pintype "passive"))
      (node (ref "R32") (pin "2") (pinfunction "2_2") (pintype "passive"))
      (node (ref "R6") (pin "2") (pinfunction "2_2") (pintype "passive"))
      (node (ref "S1") (pin "1") (pinfunction "1_1") (pintype "passive"))
      (node (ref "S2") (pin "1") (pinfunction "1_1") (pintype "passive"))
      (node (ref "S3") (pin "1") (pinfunction "1_1") (pintype "passive"))
      (node (ref "SIM1") (pin "10") (pinfunction "GND_10") (pintype "passive"))
      (node (ref "SIM1") (pin "11") (pinfunction "GND_11") (pintype "passive"))
      (node (ref "SIM1") (pin "12") (pinfunction "GND_12") (pintype "passive"))
      (node (ref "SIM1") (pin "5") (pinfunction "GND_5") (pintype "passive"))
      (node (ref "SIM1") (pin "9") (pinfunction "GND_9") (pintype "passive"))
      (node (ref "U1") (pin "1") (pinfunction "GND_1") (pintype "passive"))
      (node (ref "U1") (pin "10") (pinfunction "GND_10") (pintype "passive"))
      (node (ref "U1") (pin "27") (pinfunction "GND_27") (pintype "passive"))
      (node (ref "U1") (pin "34") (pinfunction "GND_34") (pintype "passive"))
      (node (ref "U1") (pin "36") (pinfunction "GND_36") (pintype "passive"))
      (node (ref "U1") (pin "37") (pinfunction "GND_37") (pintype "passive"))
      (node (ref "U1") (pin "40") (pinfunction "GND_40") (pintype "passive"))
      (node (ref "U1") (pin "41") (pinfunction "GND_41") (pintype "passive"))
      (node (ref "U1") (pin "45") (pinfunction "GND_45") (pintype "passive"))
      (node (ref "U1") (pin "46") (pinfunction "GND_46") (pintype "passive"))
      (node (ref "U1") (pin "47") (pinfunction "GND_47") (pintype "passive"))
      (node (ref "U1") (pin "48") (pinfunction "GND_48") (pintype "passive"))
      (node (ref "U1") (pin "70") (pinfunction "GND_70") (pintype "passive"))
      (node (ref "U1") (pin "71") (pinfunction "GND_71") (pintype "passive"))
      (node (ref "U1") (pin "72") (pinfunction "GND_72") (pintype "passive"))
      (node (ref "U1") (pin "73") (pinfunction "GND_73") (pintype "passive"))
      (node (ref "U1") (pin "88") (pinfunction "GND_88") (pintype "passive"))
      (node (ref "U1") (pin "89") (pinfunction "GND_89") (pintype "passive"))
      (node (ref "U1") (pin "90") (pinfunction "GND_90") (pintype "passive"))
      (node (ref "U1") (pin "91") (pinfunction "GND_91") (pintype "passive"))
      (node (ref "U1") (pin "92") (pinfunction "GND_92") (pintype "passive"))
      (node (ref "U1") (pin "93") (pinfunction "GND_93") (pintype "passive"))
      (node (ref "U1") (pin "94") (pinfunction "GND_94") (pintype "passive"))
      (node (ref "U1") (pin "95") (pinfunction "GND_95") (pintype "passive"))
      (node (ref "U2") (pin "7") (pinfunction "GND_7") (pintype "passive"))
      (node (ref "U2") (pin "9") (pinfunction "EP_9") (pintype "passive"))
      (node (ref "U3") (pin "57") (pinfunction "GND_57") (pintype "passive"))
      (node (ref "U4") (pin "1") (pinfunction "GND_1") (pintype "passive"))
      (node (ref "U5") (pin "4") (pinfunction "VSS_4") (pintype "passive"))
      (node (ref "U6") (pin "11") (pinfunction "GND_11") (pintype "passive"))
      (node (ref "U6") (pin "15") (pinfunction "GND_15") (pintype "passive"))
      (node (ref "U6") (pin "17") (pinfunction "EP_17") (pintype "passive"))
      (node (ref "U6") (pin "3") (pinfunction "GND_3") (pintype "passive"))
      (node (ref "U7") (pin "1") (pinfunction "GND_1") (pintype "passive"))
      (node (ref "U8") (pin "2") (pinfunction "GND_2") (pintype "passive"))
      (node (ref "U9") (pin "11") (pinfunction "GND_11") (pintype "passive"))
      (node (ref "USB1") (pin "1") (pinfunction "SH1_1") (pintype "passive"))
      (node (ref "USB1") (pin "2") (pinfunction "SH2_2") (pintype "passive"))
      (node (ref "USB1") (pin "3") (pinfunction "SH3_3") (pintype "passive"))
      (node (ref "USB1") (pin "4") (pinfunction "SH4_4") (pintype "passive"))
      (node (ref "USB1") (pin "A1") (pinfunction "GND_A1") (pintype "passive"))
      (node (ref "USB1") (pin "A12") (pinfunction "GND_A12") (pintype "passive"))
      (node (ref "USB1") (pin "B1") (pinfunction "GND_B1") (pintype "passive"))
      (node (ref "USB1") (pin "B12") (pinfunction "GND_B12") (pintype "passive"))
      (node (ref "X1") (pin "2") (pinfunction "GND_2") (pintype "passive"))
      (node (ref "X1") (pin "4") (pinfunction "GND_4") (pintype "passive"))
    )
    (net (code "41") (name "Net-(D2-A)") (class "Default")
      (node (ref "D2") (pin "1") (pinfunction "A_1") (pintype "passive"))
      (node (ref "L5") (pin "2") (pinfunction "2_2") (pintype "passive"))
      (node (ref "U2") (pin "8") (pinfunction "LX_8") (pintype "passive"))
    )
    (net (code "42") (name "Net-(D3-A)") (class "Default")
      (node (ref "D3") (pin "1") (pinfunction "A_1") (pintype "passive"))
      (node (ref "D4") (pin "1") (pinfunction "A_1") (pintype "passive"))
      (node (ref "R4") (pin "1") (pinfunction "1_1") (pintype "passive"))
    )
    (net (code "43") (name "Net-(D3-K)") (class "Default")
      (node (ref "D3") (pin "2") (pinfunction "K_2") (pintype "passive"))
      (node (ref "U2") (pin "4") (pinfunction "STDBY#_4") (pintype "passive"))
    )
    (net (code "44") (name "Net-(D4-K)") (class "Default")
      (node (ref "D4") (pin "2") (pinfunction "K_2") (pintype "passive"))
      (node (ref "U2") (pin "2") (pinfunction "CHRG#_2") (pintype "passive"))
    )
    (net (code "45") (name "Net-(D5-A)") (class "Default")
      (node (ref "D5") (pin "1") (pinfunction "A_1") (pintype "passive"))
      (node (ref "R20") (pin "1") (pinfunction "1_1") (pintype "passive"))
    )
    (net (code "46") (name "Net-(D7-A)") (class "Default")
      (node (ref "D7") (pin "1") (pinfunction "A_1") (pintype "passive"))
      (node (ref "R27") (pin "1") (pinfunction "1_1") (pintype "passive"))
    )
    (net (code "47") (name "Net-(D7-K)") (class "Default")
      (node (ref "D7") (pin "2") (pinfunction "K_2") (pintype "passive"))
      (node (ref "Q2") (pin "3") (pinfunction "C_3") (pintype "passive"))
    )
    (net (code "48") (name "Net-(IPX1-DATA)") (class "Default")
      (node (ref "IPX1") (pin "2") (pinfunction "DATA_2") (pintype "passive"))
      (node (ref "U1") (pin "35") (pinfunction "ANT_MAIN_35") (pintype "passive"))
    )
    (net (code "49") (name "Net-(Q2-B)") (class "Default")
      (node (ref "Q2") (pin "1") (pinfunction "B_1") (pintype "passive"))
      (node (ref "R30") (pin "1") (pinfunction "1_1") (pintype "passive"))
    )
    (net (code "50") (name "Net-(Q3-G)") (class "Default")
      (node (ref "Q3") (pin "1") (pinfunction "G_1") (pintype "passive"))
      (node (ref "Q4") (pin "3") (pinfunction "C_3") (pintype "passive"))
      (node (ref "R15") (pin "2") (pinfunction "2_2") (pintype "passive"))
    )
    (net (code "51") (name "Net-(Q4-B)") (class "Default")
      (node (ref "Q4") (pin "1") (pinfunction "B_1") (pintype "passive"))
      (node (ref "R16") (pin "2") (pinfunction "2_2") (pintype "passive"))
      (node (ref "R17") (pin "1") (pinfunction "1_1") (pintype "passive"))
    )
    (net (code "52") (name "Net-(Q5-D)") (class "Default")
      (node (ref "Q5") (pin "3") (pinfunction "D_3") (pintype "passive"))
      (node (ref "R21") (pin "1") (pinfunction "1_1") (pintype "passive"))
    )
    (net (code "53") (name "Net-(Q6-B)") (class "Default")
      (node (ref "Q6") (pin "1") (pinfunction "B_1") (pintype "passive"))
      (node (ref "R21") (pin "2") (pinfunction "2_2") (pintype "passive"))
    )
    (net (code "54") (name "Net-(U1-SIM_CLK)") (class "Default")
      (node (ref "R22") (pin "1") (pinfunction "1_1") (pintype "passive"))
      (node (ref "U1") (pin "13") (pinfunction "SIM_CLK_13") (pintype "passive"))
    )
    (net (code "55") (name "Net-(U1-SIM_DATA)") (class "Default")
      (node (ref "R8") (pin "1") (pinfunction "1_1") (pintype "passive"))
      (node (ref "U1") (pin "11") (pinfunction "SIM_DATA_11") (pintype "passive"))
    )
    (net (code "56") (name "Net-(U1-SIM_RST)") (class "Default")
      (node (ref "R10") (pin "1") (pinfunction "1_1") (pintype "passive"))
      (node (ref "U1") (pin "12") (pinfunction "SIM_RST_12") (pintype "passive"))
    )
    (net (code "57") (name "Net-(U1-SIM_VCC)") (class "Default")
      (node (ref "R23") (pin "1") (pinfunction "1_1") (pintype "passive"))
      (node (ref "U1") (pin "14") (pinfunction "SIM_VCC_14") (pintype "passive"))
    )
    (net (code "58") (name "Net-(U2-PROG)") (class "Default")
      (node (ref "R6") (pin "1") (pinfunction "1_1") (pintype "passive"))
      (node (ref "U2") (pin "3") (pinfunction "PROG_3") (pintype "passive"))
    )
    (net (code "59") (name "Net-(U6-OUTN)") (class "Default")
      (node (ref "R9") (pin "1") (pinfunction "1_1") (pintype "passive"))
      (node (ref "U6") (pin "10") (pinfunction "OUTN_10") (pintype "passive"))
    )
    (net (code "60") (name "Net-(U6-OUTP)") (class "Default")
      (node (ref "R12") (pin "1") (pinfunction "1_1") (pintype "passive"))
      (node (ref "U6") (pin "9") (pinfunction "OUTP_9") (pintype "passive"))
    )
    (net (code "61") (name "Net-(U7-CHIPEN)") (class "Default")
      (node (ref "R13") (pin "1") (pinfunction "1_1") (pintype "passive"))
      (node (ref "U7") (pin "4") (pinfunction "CHIPEN_4") (pintype "passive"))
    )
    (net (code "62") (name "Net-(U7-L{slash}R)") (class "Default")
      (node (ref "R14") (pin "1") (pinfunction "1_1") (pintype "passive"))
      (node (ref "U7") (pin "5") (pinfunction "L/R_5") (pintype "passive"))
    )
    (net (code "63") (name "Net-(U9-A8)") (class "Default")
      (node (ref "R32") (pin "1") (pinfunction "1_1") (pintype "passive"))
      (node (ref "U9") (pin "9") (pinfunction "A8_9") (pintype "passive"))
    )
    (net (code "64") (name "Net-(U9-B8)") (class "Default")
      (node (ref "R31") (pin "1") (pinfunction "1_1") (pintype "passive"))
      (node (ref "U9") (pin "12") (pinfunction "B8_12") (pintype "passive"))
    )
    (net (code "65") (name "Net-(USB1-CC1)") (class "Default")
      (node (ref "R1") (pin "1") (pinfunction "1_1") (pintype "passive"))
      (node (ref "USB1") (pin "A5") (pinfunction "CC1_A5") (pintype "passive"))
    )
    (net (code "66") (name "Net-(USB1-CC2)") (class "Default")
      (node (ref "R2") (pin "2") (pinfunction "2_2") (pintype "passive"))
      (node (ref "USB1") (pin "B5") (pinfunction "CC2_B5") (pintype "passive"))
    )
    (net (code "67") (name "USB_5V") (class "Default")
      (node (ref "C12") (pin "1") (pinfunction "1_1") (pintype "passive"))
      (node (ref "R4") (pin "2") (pinfunction "2_2") (pintype "passive"))
      (node (ref "U2") (pin "5") (pinfunction "VCC_5") (pintype "passive"))
      (node (ref "USB1") (pin "A4") (pinfunction "VBUS_A4") (pintype "passive"))
      (node (ref "USB1") (pin "A9") (pinfunction "VBUS_A9") (pintype "passive"))
      (node (ref "USB1") (pin "B4") (pinfunction "VBUS_B4") (pintype "passive"))
      (node (ref "USB1") (pin "B9") (pinfunction "VBUS_B9") (pintype "passive"))
    )
    (net (code "68") (name "VBAT") (class "Default")
      (node (ref "C10") (pin "1") (pinfunction "1_1") (pintype "passive"))
      (node (ref "C11") (pin "1") (pinfunction "1_1") (pintype "passive"))
      (node (ref "C9") (pin "1") (pinfunction "1_1") (pintype "passive"))
      (node (ref "L5") (pin "1") (pinfunction "1_1") (pintype "passive"))
      (node (ref "P1") (pin "1") (pinfunction "1_1") (pintype "passive"))
      (node (ref "U2") (pin "6") (pinfunction "BAT_6") (pintype "passive"))
    )
    (net (code "69") (name "VBAT_5V") (class "Default")
      (node (ref "C20") (pin "1") (pinfunction "1_1") (pintype "passive"))
      (node (ref "C21") (pin "1") (pinfunction "1_1") (pintype "passive"))
      (node (ref "C22") (pin "1") (pinfunction "1_1") (pintype "passive"))
      (node (ref "C29") (pin "2") (pinfunction "2_2") (pintype "passive"))
      (node (ref "C7") (pin "1") (pinfunction "1_1") (pintype "passive"))
      (node (ref "C8") (pin "1") (pinfunction "1_1") (pintype "passive"))
      (node (ref "D1") (pin "2") (pinfunction "K_2") (pintype "passive"))
      (node (ref "D2") (pin "2") (pinfunction "K_2") (pintype "passive"))
      (node (ref "Q3") (pin "2") (pinfunction "S_2") (pintype "passive"))
      (node (ref "Q5") (pin "2") (pinfunction "S_2") (pintype "passive"))
      (node (ref "R15") (pin "1") (pinfunction "1_1") (pintype "passive"))
      (node (ref "R19") (pin "1") (pinfunction "1_1") (pintype "passive"))
      (node (ref "U2") (pin "1") (pinfunction "VOUT_1") (pintype "passive"))
      (node (ref "U8") (pin "5") (pinfunction "VDD_5") (pintype "passive"))
    )
    (net (code "70") (name "VDD_5V") (class "Default")
      (node (ref "C15") (pin "2") (pinfunction "2_2") (pintype "passive"))
      (node (ref "C18") (pin "2") (pinfunction "2_2") (pintype "passive"))
      (node (ref "C25") (pin "1") (pinfunction "1_1") (pintype "passive"))
      (node (ref "C26") (pin "1") (pinfunction "1_1") (pintype "passive"))
      (node (ref "D8") (pin "1") (pinfunction "A_1") (pintype "passive"))
      (node (ref "LED1") (pin "4") (pinfunction "VDD_4") (pintype "passive"))
      (node (ref "Q3") (pin "3") (pinfunction "D_3") (pintype "passive"))
      (node (ref "U4") (pin "3") (pinfunction "VIN_3") (pintype "passive"))
      (node (ref "U6") (pin "7") (pinfunction "VDD_7") (pintype "passive"))
      (node (ref "U6") (pin "8") (pinfunction "VDD_8") (pintype "passive"))
    )
    (net (code "71") (name "V_4G") (class "Default")
      (node (ref "C13") (pin "1") (pinfunction "1_1") (pintype "passive"))
      (node (ref "C34") (pin "1") (pinfunction "1_1") (pintype "passive"))
      (node (ref "D8") (pin "2") (pinfunction "K_2") (pintype "passive"))
      (node (ref "U1") (pin "42") (pinfunction "VBAT_42") (pintype "passive"))
      (node (ref "U1") (pin "43") (pinfunction "VBAT_43") (pintype "passive"))
    )
    (net (code "72") (name "unconnected-(D6-Pad5)") (class "Default")
      (node (ref "D6") (pin "5") (pinfunction "5_5") (pintype "passive"))
    )
    (net (code "73") (name "unconnected-(LED1-DO-Pad1)") (class "Default")
      (node (ref "LED1") (pin "1") (pinfunction "DO_1") (pintype "passive"))
    )
    (net (code "74") (name "unconnected-(S1-Pad3)") (class "Default")
      (node (ref "S1") (pin "3") (pinfunction "3_3") (pintype "passive"))
    )
    (net (code "75") (name "unconnected-(S1-Pad4)") (class "Default")
      (node (ref "S1") (pin "4") (pinfunction "4_4") (pintype "passive"))
    )
    (net (code "76") (name "unconnected-(SIM1-CD-Pad8)") (class "Default")
      (node (ref "SIM1") (pin "8") (pinfunction "CD_8") (pintype "passive"))
    )
    (net (code "77") (name "unconnected-(SIM1-VPP-Pad6)") (class "Default")
      (node (ref "SIM1") (pin "6") (pinfunction "VPP_6") (pintype "passive"))
    )
    (net (code "78") (name "unconnected-(U1-ADC0-Pad9)") (class "Default")
      (node (ref "U1") (pin "9") (pinfunction "ADC0_9") (pintype "passive"))
    )
    (net (code "79") (name "unconnected-(U1-ADC1-Pad96)") (class "Default")
      (node (ref "U1") (pin "96") (pinfunction "ADC1_96") (pintype "passive"))
    )
    (net (code "80") (name "unconnected-(U1-DBG_RXD-Pad38)") (class "Default")
      (node (ref "U1") (pin "38") (pinfunction "DBG_RXD_38") (pintype "passive"))
    )
    (net (code "81") (name "unconnected-(U1-DBG_TXD-Pad39)") (class "Default")
      (node (ref "U1") (pin "39") (pinfunction "DBG_TXD_39") (pintype "passive"))
    )
    (net (code "82") (name "unconnected-(U1-GPIO0-Pad76)") (class "Default")
      (node (ref "U1") (pin "76") (pinfunction "GPIO0_76") (pintype "passive"))
    )
    (net (code "83") (name "unconnected-(U1-GPIO1-Pad77)") (class "Default")
      (node (ref "U1") (pin "77") (pinfunction "GPIO1_77") (pintype "passive"))
    )
    (net (code "84") (name "unconnected-(U1-GPIO2-Pad86)") (class "Default")
      (node (ref "U1") (pin "86") (pinfunction "GPIO2_86") (pintype "passive"))
    )
    (net (code "85") (name "unconnected-(U1-GPIO3-Pad87)") (class "Default")
      (node (ref "U1") (pin "87") (pinfunction "GPIO3_87") (pintype "passive"))
    )
    (net (code "86") (name "unconnected-(U1-GPIO6-Pad81)") (class "Default")
      (node (ref "U1") (pin "81") (pinfunction "GPIO6_81") (pintype "passive"))
    )
    (net (code "87") (name "unconnected-(U1-I2C0_SCL-Pad57)") (class "Default")
      (node (ref "U1") (pin "57") (pinfunction "I2C0_SCL_57") (pintype "passive"))
    )
    (net (code "88") (name "unconnected-(U1-I2C0_SDA-Pad58)") (class "Default")
      (node (ref "U1") (pin "58") (pinfunction "I2C0_SDA_58") (pintype "passive"))
    )
    (net (code "89") (name "unconnected-(U1-I2C1_SDA-Pad66)") (class "Default")
      (node (ref "U1") (pin "66") (pinfunction "I2C1_SDA_66") (pintype "passive"))
    )
    (net (code "90") (name "unconnected-(U1-I2C1_SLC-Pad67)") (class "Default")
      (node (ref "U1") (pin "67") (pinfunction "I2C1_SLC_67") (pintype "passive"))
    )
    (net (code "91") (name "unconnected-(U1-LCD_CLK-Pad53)") (class "Default")
      (node (ref "U1") (pin "53") (pinfunction "LCD_CLK_53") (pintype "passive"))
    )
    (net (code "92") (name "unconnected-(U1-LCD_CS-Pad52)") (class "Default")
      (node (ref "U1") (pin "52") (pinfunction "LCD_CS_52") (pintype "passive"))
    )
    (net (code "93") (name "unconnected-(U1-LCD_FMARK-Pad78)") (class "Default")
      (node (ref "U1") (pin "78") (pinfunction "LCD_FMARK_78") (pintype "passive"))
    )
    (net (code "94") (name "unconnected-(U1-LCD_RST-Pad49)") (class "Default")
      (node (ref "U1") (pin "49") (pinfunction "LCD_RST_49") (pintype "passive"))
    )
    (net (code "95") (name "unconnected-(U1-LCD_SDC-Pad51)") (class "Default")
      (node (ref "U1") (pin "51") (pinfunction "LCD_SDC_51") (pintype "passive"))
    )
    (net (code "96") (name "unconnected-(U1-LCD_SIO-Pad50)") (class "Default")
      (node (ref "U1") (pin "50") (pinfunction "LCD_SIO_50") (pintype "passive"))
    )
    (net (code "97") (name "unconnected-(U1-PCM_CLK-Pad30)") (class "Default")
      (node (ref "U1") (pin "30") (pinfunction "PCM_CLK_30") (pintype "passive"))
    )
    (net (code "98") (name "unconnected-(U1-PCM_IN-Pad32)") (class "Default")
      (node (ref "U1") (pin "32") (pinfunction "PCM_IN_32") (pintype "passive"))
    )
    (net (code "99") (name "unconnected-(U1-PCM_OUT-Pad33)") (class "Default")
      (node (ref "U1") (pin "33") (pinfunction "PCM_OUT_33") (pintype "passive"))
    )
    (net (code "100") (name "unconnected-(U1-PCM_SYNC-Pad31)") (class "Default")
      (node (ref "U1") (pin "31") (pinfunction "PCM_SYNC_31") (pintype "passive"))
    )
    (net (code "101") (name "unconnected-(U1-PWM0-Pad74)") (class "Default")
      (node (ref "U1") (pin "74") (pinfunction "PWM0_74") (pintype "passive"))
    )
    (net (code "102") (name "unconnected-(U1-PWM1-Pad75)") (class "Default")
      (node (ref "U1") (pin "75") (pinfunction "PWM1_75") (pintype "passive"))
    )
    (net (code "103") (name "unconnected-(U1-RESERVED-Pad2)") (class "Default")
      (node (ref "U1") (pin "2") (pinfunction "RESERVED_2") (pintype "passive"))
    )
    (net (code "104") (name "unconnected-(U1-RESERVED-Pad3)") (class "Default")
      (node (ref "U1") (pin "3") (pinfunction "RESERVED_3") (pintype "passive"))
    )
    (net (code "105") (name "unconnected-(U1-RESERVED-Pad4)") (class "Default")
      (node (ref "U1") (pin "4") (pinfunction "RESERVED_4") (pintype "passive"))
    )
    (net (code "106") (name "unconnected-(U1-RESERVED-Pad5)") (class "Default")
      (node (ref "U1") (pin "5") (pinfunction "RESERVED_5") (pintype "passive"))
    )
    (net (code "107") (name "unconnected-(U1-RESERVED-Pad6)") (class "Default")
      (node (ref "U1") (pin "6") (pinfunction "RESERVED_6") (pintype "passive"))
    )
    (net (code "108") (name "unconnected-(U1-RESERVED-Pad26)") (class "Default")
      (node (ref "U1") (pin "26") (pinfunction "RESERVED_26") (pintype "passive"))
    )
    (net (code "109") (name "unconnected-(U1-RESERVED-Pad44)") (class "Default")
      (node (ref "U1") (pin "44") (pinfunction "RESERVED_44") (pintype "passive"))
    )
    (net (code "110") (name "unconnected-(U1-RESERVED-Pad54)") (class "Default")
      (node (ref "U1") (pin "54") (pinfunction "RESERVED_54") (pintype "passive"))
    )
    (net (code "111") (name "unconnected-(U1-RESERVED-Pad55)") (class "Default")
      (node (ref "U1") (pin "55") (pinfunction "RESERVED_55") (pintype "passive"))
    )
    (net (code "112") (name "unconnected-(U1-RESERVED-Pad56)") (class "Default")
      (node (ref "U1") (pin "56") (pinfunction "RESERVED_56") (pintype "passive"))
    )
    (net (code "113") (name "unconnected-(U1-RESERVED-Pad62)") (class "Default")
      (node (ref "U1") (pin "62") (pinfunction "RESERVED_62") (pintype "passive"))
    )
    (net (code "114") (name "unconnected-(U1-RESERVED-Pad63)") (class "Default")
      (node (ref "U1") (pin "63") (pinfunction "RESERVED_63") (pintype "passive"))
    )
    (net (code "115") (name "unconnected-(U1-RESERVED-Pad64)") (class "Default")
      (node (ref "U1") (pin "64") (pinfunction "RESERVED_64") (pintype "passive"))
    )
    (net (code "116") (name "unconnected-(U1-RESERVED-Pad65)") (class "Default")
      (node (ref "U1") (pin "65") (pinfunction "RESERVED_65") (pintype "passive"))
    )
    (net (code "117") (name "unconnected-(U1-RESERVED-Pad68)") (class "Default")
      (node (ref "U1") (pin "68") (pinfunction "RESERVED_68") (pintype "passive"))
    )
    (net (code "118") (name "unconnected-(U1-RESERVED-Pad69)") (class "Default")
      (node (ref "U1") (pin "69") (pinfunction "RESERVED_69") (pintype "passive"))
    )
    (net (code "119") (name "unconnected-(U1-RESERVED-Pad80)") (class "Default")
      (node (ref "U1") (pin "80") (pinfunction "RESERVED_80") (pintype "passive"))
    )
    (net (code "120") (name "unconnected-(U1-RESERVED-Pad83)") (class "Default")
      (node (ref "U1") (pin "83") (pinfunction "RESERVED_83") (pintype "passive"))
    )
    (net (code "121") (name "unconnected-(U1-RESERVED-Pad84)") (class "Default")
      (node (ref "U1") (pin "84") (pinfunction "RESERVED_84") (pintype "passive"))
    )
    (net (code "122") (name "unconnected-(U1-RESERVED-Pad85)") (class "Default")
      (node (ref "U1") (pin "85") (pinfunction "RESERVED_85") (pintype "passive"))
    )
    (net (code "123") (name "unconnected-(U1-RESERVED-Pad97)") (class "Default")
      (node (ref "U1") (pin "97") (pinfunction "RESERVED_97") (pintype "passive"))
    )
    (net (code "124") (name "unconnected-(U1-RESERVED-Pad98)") (class "Default")
      (node (ref "U1") (pin "98") (pinfunction "RESERVED_98") (pintype "passive"))
    )
    (net (code "125") (name "unconnected-(U1-RESERVED-Pad99)") (class "Default")
      (node (ref "U1") (pin "99") (pinfunction "RESERVED_99") (pintype "passive"))
    )
    (net (code "126") (name "unconnected-(U1-RESERVED-Pad100)") (class "Default")
      (node (ref "U1") (pin "100") (pinfunction "RESERVED_100") (pintype "passive"))
    )
    (net (code "127") (name "unconnected-(U1-RESERVED-Pad101)") (class "Default")
      (node (ref "U1") (pin "101") (pinfunction "RESERVED_101") (pintype "passive"))
    )
    (net (code "128") (name "unconnected-(U1-RESERVED-Pad102)") (class "Default")
      (node (ref "U1") (pin "102") (pinfunction "RESERVED_102") (pintype "passive"))
    )
    (net (code "129") (name "unconnected-(U1-RESERVED-Pad103)") (class "Default")
      (node (ref "U1") (pin "103") (pinfunction "RESERVED_103") (pintype "passive"))
    )
    (net (code "130") (name "unconnected-(U1-RESERVED-Pad104)") (class "Default")
      (node (ref "U1") (pin "104") (pinfunction "RESERVED_104") (pintype "passive"))
    )
    (net (code "131") (name "unconnected-(U1-RESERVED-Pad105)") (class "Default")
      (node (ref "U1") (pin "105") (pinfunction "RESERVED_105") (pintype "passive"))
    )
    (net (code "132") (name "unconnected-(U1-RESERVED-Pad106)") (class "Default")
      (node (ref "U1") (pin "106") (pinfunction "RESERVED_106") (pintype "passive"))
    )
    (net (code "133") (name "unconnected-(U1-RESET-Pad15)") (class "Default")
      (node (ref "U1") (pin "15") (pinfunction "RESET_15") (pintype "passive"))
    )
    (net (code "134") (name "unconnected-(U1-SIM_DET-Pad79)") (class "Default")
      (node (ref "U1") (pin "79") (pinfunction "SIM_DET_79") (pintype "passive"))
    )
    (net (code "135") (name "unconnected-(U1-STATE{slash}GPIO5-Pad25)") (class "Default")
      (node (ref "U1") (pin "25") (pinfunction "STATE/GPIO5_25") (pintype "passive"))
    )
    (net (code "136") (name "unconnected-(U1-UART0_CTS-Pad22)") (class "Default")
      (node (ref "U1") (pin "22") (pinfunction "UART0_CTS_22") (pintype "passive"))
    )
    (net (code "137") (name "unconnected-(U1-UART0_DCD-Pad21)") (class "Default")
      (node (ref "U1") (pin "21") (pinfunction "UART0_DCD_21") (pintype "passive"))
    )
    (net (code "138") (name "unconnected-(U1-UART0_DTR-Pad19)") (class "Default")
      (node (ref "U1") (pin "19") (pinfunction "UART0_DTR_19") (pintype "passive"))
    )
    (net (code "139") (name "unconnected-(U1-UART0_RI-Pad20)") (class "Default")
      (node (ref "U1") (pin "20") (pinfunction "UART0_RI_20") (pintype "passive"))
    )
    (net (code "140") (name "unconnected-(U1-UART0_RTS-Pad23)") (class "Default")
      (node (ref "U1") (pin "23") (pinfunction "UART0_RTS_23") (pintype "passive"))
    )
    (net (code "141") (name "unconnected-(U1-UART1_RXD-Pad28)") (class "Default")
      (node (ref "U1") (pin "28") (pinfunction "UART1_RXD_28") (pintype "passive"))
    )
    (net (code "142") (name "unconnected-(U1-UART1_TXD-Pad29)") (class "Default")
      (node (ref "U1") (pin "29") (pinfunction "UART1_TXD_29") (pintype "passive"))
    )
    (net (code "143") (name "unconnected-(U1-USB_BOOT-Pad82)") (class "Default")
      (node (ref "U1") (pin "82") (pinfunction "USB_BOOT_82") (pintype "passive"))
    )
    (net (code "144") (name "unconnected-(U1-USB_DM-Pad60)") (class "Default")
      (node (ref "U1") (pin "60") (pinfunction "USB_DM_60") (pintype "passive"))
    )
    (net (code "145") (name "unconnected-(U1-USB_DP-Pad59)") (class "Default")
      (node (ref "U1") (pin "59") (pinfunction "USB_DP_59") (pintype "passive"))
    )
    (net (code "146") (name "unconnected-(U1-USB_VBUS-Pad61)") (class "Default")
      (node (ref "U1") (pin "61") (pinfunction "USB_VBUS_61") (pintype "passive"))
    )
    (net (code "147") (name "unconnected-(U1-VCC_CAMA-Pad8)") (class "Default")
      (node (ref "U1") (pin "8") (pinfunction "VCC_CAMA_8") (pintype "passive"))
    )
    (net (code "148") (name "unconnected-(U3-GPIO4-Pad9)") (class "Default")
      (node (ref "U3") (pin "9") (pinfunction "GPIO4_9") (pintype "passive"))
    )
    (net (code "149") (name "unconnected-(U3-GPIO5-Pad10)") (class "Default")
      (node (ref "U3") (pin "10") (pinfunction "GPIO5_10") (pintype "passive"))
    )
    (net (code "150") (name "unconnected-(U3-GPIO6-Pad11)") (class "Default")
      (node (ref "U3") (pin "11") (pinfunction "GPIO6_11") (pintype "passive"))
    )
    (net (code "151") (name "unconnected-(U3-GPIO7-Pad12)") (class "Default")
      (node (ref "U3") (pin "12") (pinfunction "GPIO7_12") (pintype "passive"))
    )
    (net (code "152") (name "unconnected-(U3-GPIO8-Pad13)") (class "Default")
      (node (ref "U3") (pin "13") (pinfunction "GPIO8_13") (pintype "passive"))
    )
    (net (code "153") (name "unconnected-(U3-GPIO9-Pad14)") (class "Default")
      (node (ref "U3") (pin "14") (pinfunction "GPIO9_14") (pintype "passive"))
    )
    (net (code "154") (name "unconnected-(U3-GPIO10-Pad15)") (class "Default")
      (node (ref "U3") (pin "15") (pinfunction "GPIO10_15") (pintype "passive"))
    )
    (net (code "155") (name "unconnected-(U3-GPIO13-Pad18)") (class "Default")
      (node (ref "U3") (pin "18") (pinfunction "GPIO13_18") (pintype "passive"))
    )
    (net (code "156") (name "unconnected-(U3-GPIO14-Pad19)") (class "Default")
      (node (ref "U3") (pin "19") (pinfunction "GPIO14_19") (pintype "passive"))
    )
    (net (code "157") (name "unconnected-(U3-GPIO17-Pad23)") (class "Default")
      (node (ref "U3") (pin "23") (pinfunction "GPIO17_23") (pintype "passive"))
    )
    (net (code "158") (name "unconnected-(U3-GPIO18-Pad24)") (class "Default")
      (node (ref "U3") (pin "24") (pinfunction "GPIO18_24") (pintype "passive"))
    )
    (net (code "159") (name "unconnected-(U3-GPIO21-Pad27)") (class "Default")
      (node (ref "U3") (pin "27") (pinfunction "GPIO21_27") (pintype "passive"))
    )
    (net (code "160") (name "unconnected-(U3-GPIO33-Pad38)") (class "Default")
      (node (ref "U3") (pin "38") (pinfunction "GPIO33_38") (pintype "passive"))
    )
    (net (code "161") (name "unconnected-(U3-GPIO34-Pad39)") (class "Default")
      (node (ref "U3") (pin "39") (pinfunction "GPIO34_39") (pintype "passive"))
    )
    (net (code "162") (name "unconnected-(U3-GPIO35-Pad40)") (class "Default")
      (node (ref "U3") (pin "40") (pinfunction "GPIO35_40") (pintype "passive"))
    )
    (net (code "163") (name "unconnected-(U3-GPIO36-Pad41)") (class "Default")
      (node (ref "U3") (pin "41") (pinfunction "GPIO36_41") (pintype "passive"))
    )
    (net (code "164") (name "unconnected-(U3-GPIO37-Pad42)") (class "Default")
      (node (ref "U3") (pin "42") (pinfunction "GPIO37_42") (pintype "passive"))
    )
    (net (code "165") (name "unconnected-(U3-LNA_IN-Pad1)") (class "Default")
      (node (ref "U3") (pin "1") (pinfunction "LNA_IN_1") (pintype "passive"))
    )
    (net (code "166") (name "unconnected-(U3-MTCK-Pad44)") (class "Default")
      (node (ref "U3") (pin "44") (pinfunction "MTCK_44") (pintype "passive"))
    )
    (net (code "167") (name "unconnected-(U3-MTDI-Pad47)") (class "Default")
      (node (ref "U3") (pin "47") (pinfunction "MTDI_47") (pintype "passive"))
    )
    (net (code "168") (name "unconnected-(U3-MTDO-Pad45)") (class "Default")
      (node (ref "U3") (pin "45") (pinfunction "MTDO_45") (pintype "passive"))
    )
    (net (code "169") (name "unconnected-(U3-MTMS-Pad48)") (class "Default")
      (node (ref "U3") (pin "48") (pinfunction "MTMS_48") (pintype "passive"))
    )
    (net (code "170") (name "unconnected-(U3-SPICS1-Pad28)") (class "Default")
      (node (ref "U3") (pin "28") (pinfunction "SPICS1_28") (pintype "passive"))
    )
    (net (code "171") (name "unconnected-(U3-U0RXD-Pad50)") (class "Default")
      (node (ref "U3") (pin "50") (pinfunction "U0RXD_50") (pintype "passive"))
    )
    (net (code "172") (name "unconnected-(U3-U0TXD-Pad49)") (class "Default")
      (node (ref "U3") (pin "49") (pinfunction "U0TXD_49") (pintype "passive"))
    )
    (net (code "173") (name "unconnected-(U3-XTAL_32K_N-Pad22)") (class "Default")
      (node (ref "U3") (pin "22") (pinfunction "XTAL_32K_N_22") (pintype "passive"))
    )
    (net (code "174") (name "unconnected-(U3-XTAL_32K_P-Pad21)") (class "Default")
      (node (ref "U3") (pin "21") (pinfunction "XTAL_32K_P_21") (pintype "passive"))
    )
    (net (code "175") (name "unconnected-(U6-N.C.-Pad5)") (class "Default")
      (node (ref "U6") (pin "5") (pinfunction "N.C._5") (pintype "passive+no_connect"))
    )
    (net (code "176") (name "unconnected-(U6-N.C.-Pad6)") (class "Default")
      (node (ref "U6") (pin "6") (pinfunction "N.C._6") (pintype "passive+no_connect"))
    )
    (net (code "177") (name "unconnected-(U6-N.C.-Pad12)") (class "Default")
      (node (ref "U6") (pin "12") (pinfunction "N.C._12") (pintype "passive+no_connect"))
    )
    (net (code "178") (name "unconnected-(U6-N.C.-Pad13)") (class "Default")
      (node (ref "U6") (pin "13") (pinfunction "N.C._13") (pintype "passive+no_connect"))
    )
    (net (code "179") (name "unconnected-(U7-N{slash}C-Pad2)") (class "Default")
      (node (ref "U7") (pin "2") (pinfunction "N/C_2") (pintype "passive+no_connect"))
    )
    (net (code "180") (name "unconnected-(U8-NC-Pad4)") (class "Default")
      (node (ref "U8") (pin "4") (pinfunction "NC_4") (pintype "passive+no_connect"))
    )
    (net (code "181") (name "unconnected-(U8-NC-Pad6)") (class "Default")
      (node (ref "U8") (pin "6") (pinfunction "NC_6") (pintype "passive+no_connect"))
    )
    (net (code "182") (name "unconnected-(U9-A1-Pad1)") (class "Default")
      (node (ref "U9") (pin "1") (pinfunction "A1_1") (pintype "passive"))
    )
    (net (code "183") (name "unconnected-(U9-A2-Pad3)") (class "Default")
      (node (ref "U9") (pin "3") (pinfunction "A2_3") (pintype "passive"))
    )
    (net (code "184") (name "unconnected-(U9-A3-Pad4)") (class "Default")
      (node (ref "U9") (pin "4") (pinfunction "A3_4") (pintype "passive"))
    )
    (net (code "185") (name "unconnected-(U9-A4-Pad5)") (class "Default")
      (node (ref "U9") (pin "5") (pinfunction "A4_5") (pintype "passive"))
    )
    (net (code "186") (name "unconnected-(U9-A5-Pad6)") (class "Default")
      (node (ref "U9") (pin "6") (pinfunction "A5_6") (pintype "passive"))
    )
    (net (code "187") (name "unconnected-(U9-B1-Pad20)") (class "Default")
      (node (ref "U9") (pin "20") (pinfunction "B1_20") (pintype "passive"))
    )
    (net (code "188") (name "unconnected-(U9-B2-Pad18)") (class "Default")
      (node (ref "U9") (pin "18") (pinfunction "B2_18") (pintype "passive"))
    )
    (net (code "189") (name "unconnected-(U9-B3-Pad17)") (class "Default")
      (node (ref "U9") (pin "17") (pinfunction "B3_17") (pintype "passive"))
    )
    (net (code "190") (name "unconnected-(U9-B4-Pad16)") (class "Default")
      (node (ref "U9") (pin "16") (pinfunction "B4_16") (pintype "passive"))
    )
    (net (code "191") (name "unconnected-(U9-B5-Pad15)") (class "Default")
      (node (ref "U9") (pin "15") (pinfunction "B5_15") (pintype "passive"))
    )
    (net (code "192") (name "unconnected-(USB1-RX1+-PadB11)") (class "Default")
      (node (ref "USB1") (pin "B11") (pinfunction "RX1+_B11") (pintype "passive"))
    )
    (net (code "193") (name "unconnected-(USB1-RX1--PadB10)") (class "Default")
      (node (ref "USB1") (pin "B10") (pinfunction "RX1-_B10") (pintype "passive"))
    )
    (net (code "194") (name "unconnected-(USB1-RX2+-PadA11)") (class "Default")
      (node (ref "USB1") (pin "A11") (pinfunction "RX2+_A11") (pintype "passive"))
    )
    (net (code "195") (name "unconnected-(USB1-RX2--PadA10)") (class "Default")
      (node (ref "USB1") (pin "A10") (pinfunction "RX2-_A10") (pintype "passive"))
    )
    (net (code "196") (name "unconnected-(USB1-SBU1-PadA8)") (class "Default")
      (node (ref "USB1") (pin "A8") (pinfunction "SBU1_A8") (pintype "passive"))
    )
    (net (code "197") (name "unconnected-(USB1-SBU2-PadB8)") (class "Default")
      (node (ref "USB1") (pin "B8") (pinfunction "SBU2_B8") (pintype "passive"))
    )
    (net (code "198") (name "unconnected-(USB1-TX1+-PadA2)") (class "Default")
      (node (ref "USB1") (pin "A2") (pinfunction "TX1+_A2") (pintype "passive"))
    )
    (net (code "199") (name "unconnected-(USB1-TX1--PadA3)") (class "Default")
      (node (ref "USB1") (pin "A3") (pinfunction "TX1-_A3") (pintype "passive"))
    )
    (net (code "200") (name "unconnected-(USB1-TX2+-PadB2)") (class "Default")
      (node (ref "USB1") (pin "B2") (pinfunction "TX2+_B2") (pintype "passive"))
    )
    (net (code "201") (name "unconnected-(USB1-TX2--PadB3)") (class "Default")
      (node (ref "USB1") (pin "B3") (pinfunction "TX2-_B3") (pintype "passive"))
    )
  )
)
